# STM32_V1_0.net
KiCad netlist of a schematic drawn in Altium Designer
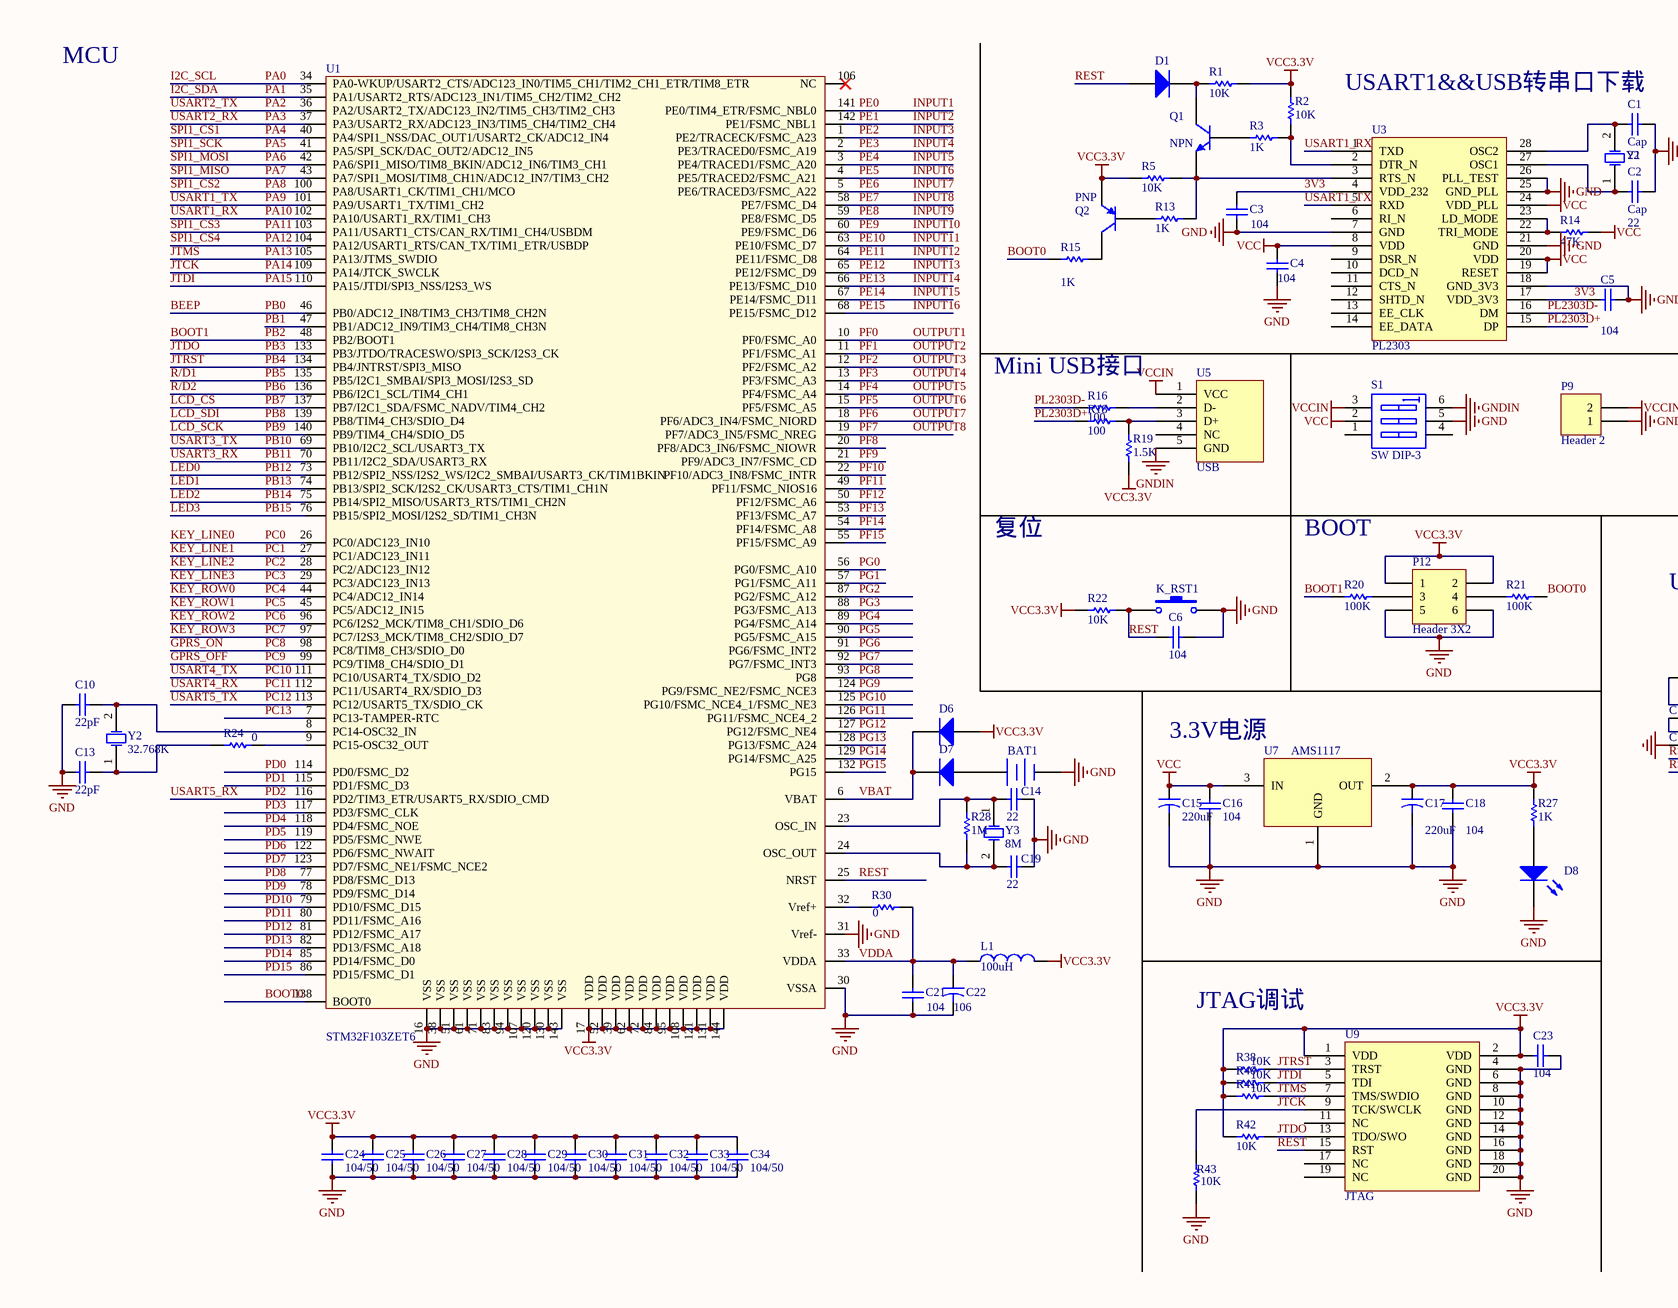
[diagram p0: STM32主板V1.0.SchDoc, left]
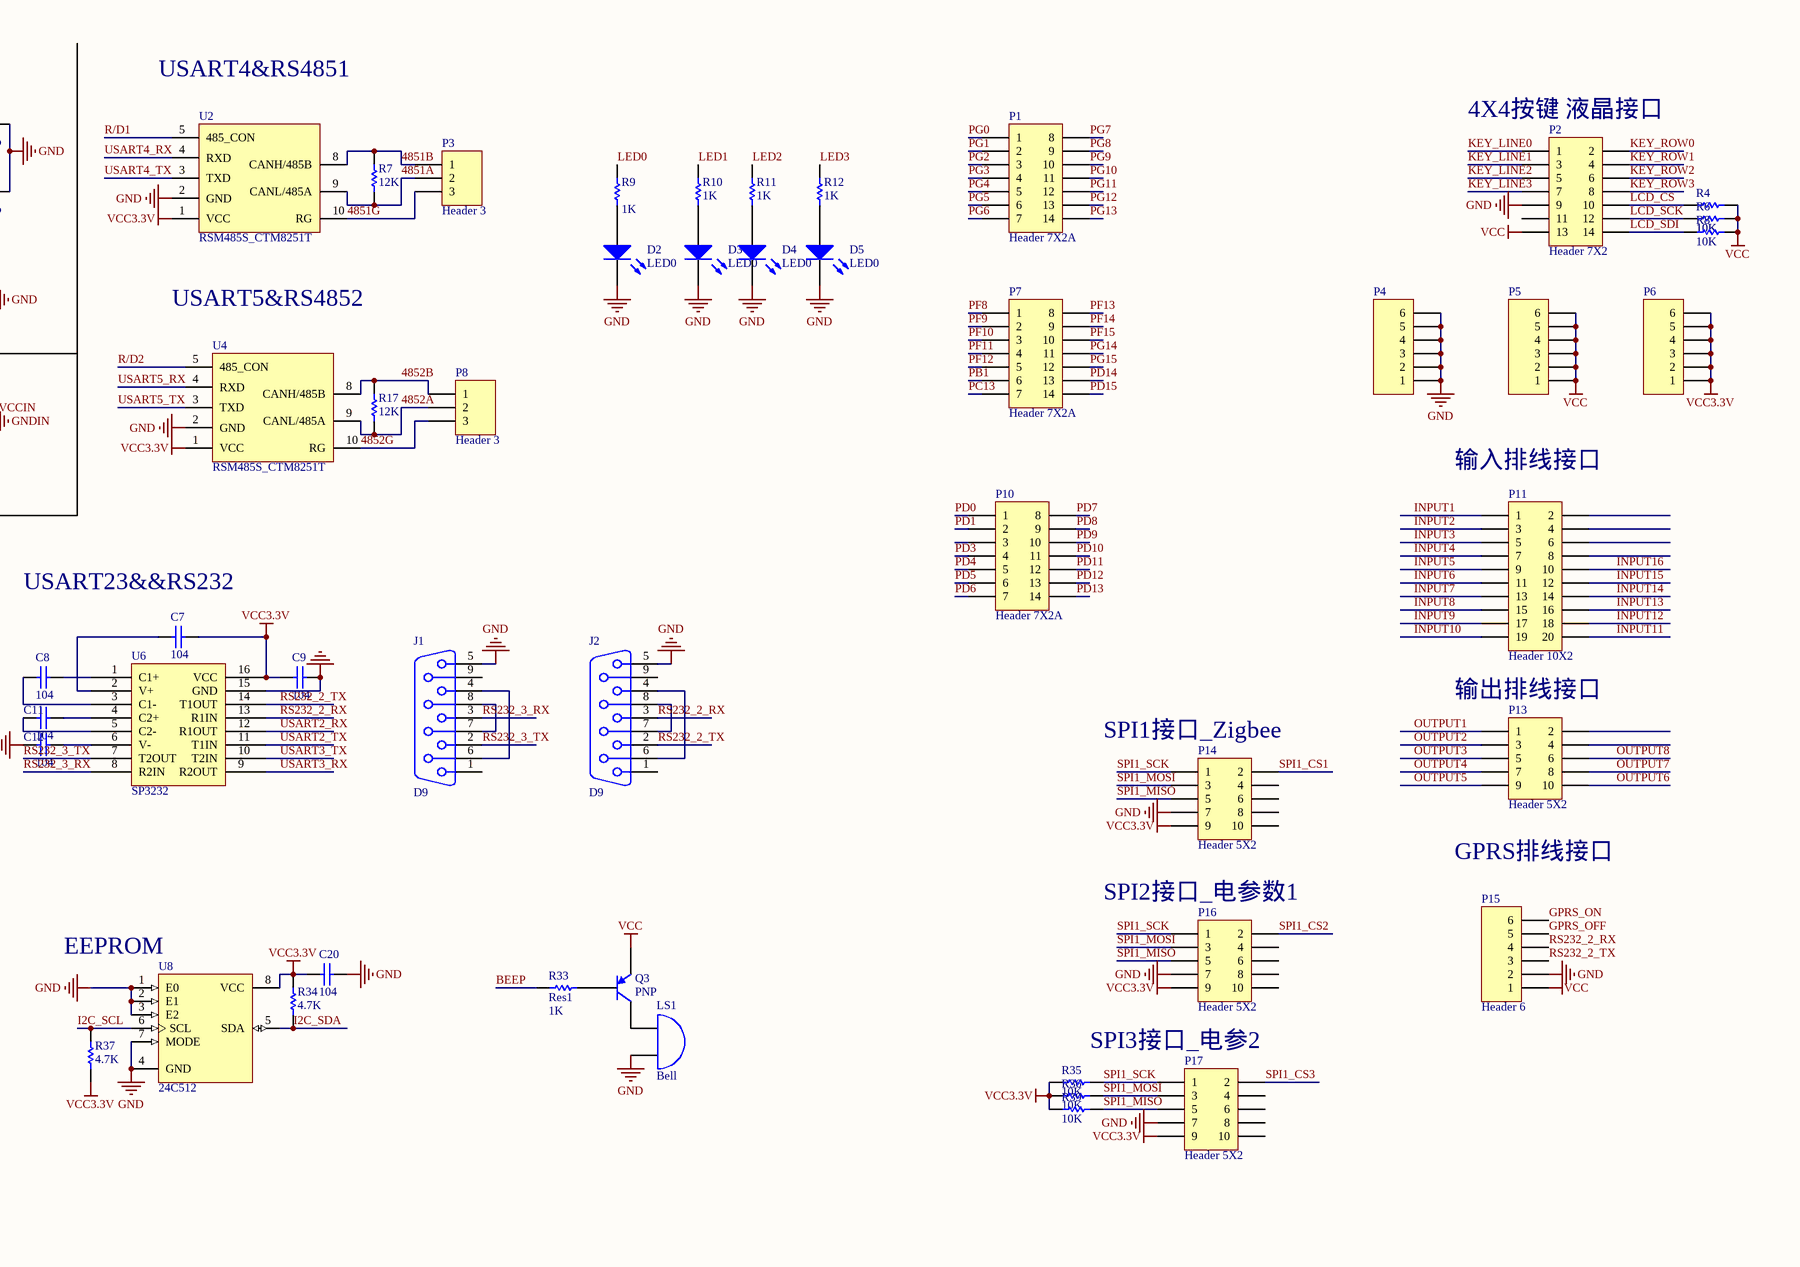
[diagram p1: STM32主板V1.0.SchDoc, right]

(export (version "E")
  (design (tool "Eeschema 10.0.6"))
  (components
    (comp (ref "BAT1")
      (value "Battery")
      (footprint "电池槽")
      (description "Multicell Battery")
      (fields (field (name "PUBLISHER") "Altium Limited"))
      (libsource (lib "Miscellaneous Devices") (part "Battery"))
    )
    (comp (ref "C1")
      (value "Cap")
      (footprint "普通贴片电容")
      (description "Capacitor")
      (fields (field (name "ALTIUM_VALUE") "22") (field (name "PUBLISHER") "Altium Limited"))
      (libsource (lib "Miscellaneous Devices") (part "Cap"))
    )
    (comp (ref "C2")
      (value "Cap")
      (footprint "普通贴片电容")
      (description "Capacitor")
      (fields (field (name "ALTIUM_VALUE") "22") (field (name "PUBLISHER") "Altium Limited"))
      (libsource (lib "Miscellaneous Devices") (part "Cap"))
    )
    (comp (ref "C3")
      (value "104")
      (footprint "普通贴片电容")
      (description "Capacitor")
      (fields (field (name "Comment") "Cap") (field (name "PUBLISHER") "Altium Limited"))
      (libsource (lib "Miscellaneous Devices") (part "Cap"))
    )
    (comp (ref "C4")
      (value "104")
      (footprint "普通贴片电容")
      (description "Capacitor")
      (fields (field (name "Comment") "Cap") (field (name "PUBLISHER") "Altium Limited"))
      (libsource (lib "Miscellaneous Devices") (part "Cap"))
    )
    (comp (ref "C5")
      (value "104")
      (footprint "普通贴片电容")
      (description "Capacitor")
      (fields (field (name "Comment") "Cap") (field (name "PUBLISHER") "Altium Limited"))
      (libsource (lib "Miscellaneous Devices") (part "Cap"))
    )
    (comp (ref "C6")
      (value "104")
      (footprint "普通贴片电容")
      (description "Capacitor")
      (fields (field (name "Comment") "Cap") (field (name "PUBLISHER") "Altium Limited"))
      (libsource (lib "Miscellaneous Devices") (part "Cap"))
    )
    (comp (ref "C7")
      (value "104")
      (footprint "普通贴片电容")
      (description "Capacitor (Semiconductor SIM Model)")
      (fields (field (name "PUBLISHER") "Altium Limited"))
      (libsource (lib "Miscellaneous Devices") (part "Cap Semi"))
    )
    (comp (ref "C8")
      (value "104")
      (footprint "普通贴片电容")
      (description "Capacitor (Semiconductor SIM Model)")
      (fields (field (name "PUBLISHER") "Altium Limited"))
      (libsource (lib "Miscellaneous Devices") (part "Cap Semi"))
    )
    (comp (ref "C9")
      (value "104")
      (footprint "普通贴片电容")
      (description "Capacitor (Semiconductor SIM Model)")
      (fields (field (name "PUBLISHER") "Altium Limited"))
      (libsource (lib "Miscellaneous Devices") (part "Cap Semi"))
    )
    (comp (ref "C10")
      (value "22pF")
      (footprint "普通贴片电容")
      (description "Capacitor")
      (fields (field (name "Comment") "Cap") (field (name "PUBLISHER") "Altium Limited"))
      (libsource (lib "Miscellaneous Devices") (part "Cap"))
    )
    (comp (ref "C11")
      (value "104")
      (footprint "普通贴片电容")
      (description "Capacitor (Semiconductor SIM Model)")
      (fields (field (name "PUBLISHER") "Altium Limited"))
      (libsource (lib "Miscellaneous Devices") (part "Cap Semi"))
    )
    (comp (ref "C12")
      (value "104")
      (footprint "普通贴片电容")
      (description "Capacitor (Semiconductor SIM Model)")
      (fields (field (name "PUBLISHER") "Altium Limited"))
      (libsource (lib "Miscellaneous Devices") (part "Cap Semi"))
    )
    (comp (ref "C13")
      (value "22pF")
      (footprint "普通贴片电容")
      (description "Capacitor")
      (fields (field (name "Comment") "Cap") (field (name "PUBLISHER") "Altium Limited"))
      (libsource (lib "Miscellaneous Devices") (part "Cap"))
    )
    (comp (ref "C14")
      (value "22")
      (footprint "普通贴片电容")
      (description "Capacitor")
      (fields (field (name "PUBLISHER") "Altium Limited"))
      (libsource (lib "Miscellaneous Devices") (part "Cap"))
    )
    (comp (ref "C15")
      (value "220uF")
      (footprint "电容100uf")
      (description "Capacitor")
      (fields (field (name "Comment") "Cap2") (field (name "PUBLISHER") "Altium Limited"))
      (libsource (lib "Miscellaneous Devices") (part "Cap2"))
    )
    (comp (ref "C16")
      (value "104")
      (footprint "普通贴片电容")
      (description "Capacitor")
      (fields (field (name "Comment") "Cap") (field (name "PUBLISHER") "Altium Limited"))
      (libsource (lib "Miscellaneous Devices") (part "Cap"))
    )
    (comp (ref "C17")
      (value "220uF")
      (footprint "电容100uf")
      (description "Capacitor")
      (fields (field (name "Comment") "Cap2") (field (name "PUBLISHER") "Altium Limited"))
      (libsource (lib "Miscellaneous Devices") (part "Cap2"))
    )
    (comp (ref "C18")
      (value "104")
      (footprint "普通贴片电容")
      (description "Capacitor")
      (fields (field (name "Comment") "Cap") (field (name "PUBLISHER") "Altium Limited"))
      (libsource (lib "Miscellaneous Devices") (part "Cap"))
    )
    (comp (ref "C19")
      (value "22")
      (footprint "普通贴片电容")
      (description "Capacitor")
      (fields (field (name "PUBLISHER") "Altium Limited"))
      (libsource (lib "Miscellaneous Devices") (part "Cap"))
    )
    (comp (ref "C20")
      (value "104")
      (footprint "普通贴片电容")
      (description "Capacitor")
      (fields (field (name "Comment") "Cap") (field (name "PUBLISHER") "Altium Limited"))
      (libsource (lib "Miscellaneous Devices") (part "Cap"))
    )
    (comp (ref "C21")
      (value "104")
      (footprint "普通贴片电容")
      (description "Capacitor")
      (fields (field (name "Comment") "Cap") (field (name "PUBLISHER") "Altium Limited"))
      (libsource (lib "Miscellaneous Devices") (part "Cap"))
    )
    (comp (ref "C22")
      (value "106")
      (footprint "普通贴片电容")
      (description "Capacitor")
      (fields (field (name "Comment") "Cap2") (field (name "PUBLISHER") "Altium Limited"))
      (libsource (lib "Miscellaneous Devices") (part "Cap2"))
    )
    (comp (ref "C23")
      (value "104")
      (footprint "普通贴片电容")
      (description "Capacitor")
      (fields (field (name "Comment") "Cap") (field (name "PUBLISHER") "Altium Limited"))
      (libsource (lib "Miscellaneous Devices") (part "Cap"))
    )
    (comp (ref "C24")
      (value "104/50")
      (footprint "普通贴片电容")
      (description "Capacitor")
      (fields (field (name "Comment") "Cap") (field (name "PUBLISHER") "Altium Limited"))
      (libsource (lib "Miscellaneous Devices") (part "Cap"))
    )
    (comp (ref "C25")
      (value "104/50")
      (footprint "普通贴片电容")
      (description "Capacitor")
      (fields (field (name "Comment") "Cap") (field (name "PUBLISHER") "Altium Limited"))
      (libsource (lib "Miscellaneous Devices") (part "Cap"))
    )
    (comp (ref "C26")
      (value "104/50")
      (footprint "普通贴片电容")
      (description "Capacitor")
      (fields (field (name "Comment") "Cap") (field (name "PUBLISHER") "Altium Limited"))
      (libsource (lib "Miscellaneous Devices") (part "Cap"))
    )
    (comp (ref "C27")
      (value "104/50")
      (footprint "普通贴片电容")
      (description "Capacitor")
      (fields (field (name "Comment") "Cap") (field (name "PUBLISHER") "Altium Limited"))
      (libsource (lib "Miscellaneous Devices") (part "Cap"))
    )
    (comp (ref "C28")
      (value "104/50")
      (footprint "普通贴片电容")
      (description "Capacitor")
      (fields (field (name "Comment") "Cap") (field (name "PUBLISHER") "Altium Limited"))
      (libsource (lib "Miscellaneous Devices") (part "Cap"))
    )
    (comp (ref "C29")
      (value "104/50")
      (footprint "普通贴片电容")
      (description "Capacitor")
      (fields (field (name "Comment") "Cap") (field (name "PUBLISHER") "Altium Limited"))
      (libsource (lib "Miscellaneous Devices") (part "Cap"))
    )
    (comp (ref "C30")
      (value "104/50")
      (footprint "普通贴片电容")
      (description "Capacitor")
      (fields (field (name "Comment") "Cap") (field (name "PUBLISHER") "Altium Limited"))
      (libsource (lib "Miscellaneous Devices") (part "Cap"))
    )
    (comp (ref "C31")
      (value "104/50")
      (footprint "普通贴片电容")
      (description "Capacitor")
      (fields (field (name "Comment") "Cap") (field (name "PUBLISHER") "Altium Limited"))
      (libsource (lib "Miscellaneous Devices") (part "Cap"))
    )
    (comp (ref "C32")
      (value "104/50")
      (footprint "普通贴片电容")
      (description "Capacitor")
      (fields (field (name "Comment") "Cap") (field (name "PUBLISHER") "Altium Limited"))
      (libsource (lib "Miscellaneous Devices") (part "Cap"))
    )
    (comp (ref "C33")
      (value "104/50")
      (footprint "普通贴片电容")
      (description "Capacitor")
      (fields (field (name "Comment") "Cap") (field (name "PUBLISHER") "Altium Limited"))
      (libsource (lib "Miscellaneous Devices") (part "Cap"))
    )
    (comp (ref "C34")
      (value "104/50")
      (footprint "普通贴片电容")
      (description "Capacitor")
      (fields (field (name "Comment") "Cap") (field (name "PUBLISHER") "Altium Limited"))
      (libsource (lib "Miscellaneous Devices") (part "Cap"))
    )
    (comp (ref "D1")
      (value "Diode")
      (footprint "贴片二极管")
      (description "Default Diode")
      (fields (field (name "PUBLISHER") "Altium Limited"))
      (libsource (lib "Miscellaneous Devices") (part "Diode"))
    )
    (comp (ref "D2")
      (value "LED0")
      (footprint "贴片LED灯")
      (description "Typical INFRARED GaAs LED")
      (fields (field (name "PUBLISHER") "Altium Limited"))
      (libsource (lib "Miscellaneous Devices") (part "LED0"))
    )
    (comp (ref "D3")
      (value "LED0")
      (footprint "贴片LED灯")
      (description "Typical INFRARED GaAs LED")
      (fields (field (name "PUBLISHER") "Altium Limited"))
      (libsource (lib "Miscellaneous Devices") (part "LED0"))
    )
    (comp (ref "D4")
      (value "LED0")
      (footprint "贴片LED灯")
      (description "Typical INFRARED GaAs LED")
      (fields (field (name "PUBLISHER") "Altium Limited"))
      (libsource (lib "Miscellaneous Devices") (part "LED0"))
    )
    (comp (ref "D5")
      (value "LED0")
      (footprint "贴片LED灯")
      (description "Typical INFRARED GaAs LED")
      (fields (field (name "PUBLISHER") "Altium Limited"))
      (libsource (lib "Miscellaneous Devices") (part "LED0"))
    )
    (comp (ref "D6")
      (value "Diode 1N4148")
      (footprint "贴片二极管")
      (description "High Conductance Fast Diode")
      (fields (field (name "PUBLISHER") "Altium Limited"))
      (libsource (lib "Miscellaneous Devices") (part "Diode 1N4148"))
    )
    (comp (ref "D7")
      (value "Diode 1N4148")
      (footprint "贴片二极管")
      (description "High Conductance Fast Diode")
      (fields (field (name "PUBLISHER") "Altium Limited"))
      (libsource (lib "Miscellaneous Devices") (part "Diode 1N4148"))
    )
    (comp (ref "D8")
      (value "LED0")
      (footprint "贴片LED灯")
      (description "Typical INFRARED GaAs LED")
      (fields (field (name "PUBLISHER") "Altium Limited"))
      (libsource (lib "Miscellaneous Devices") (part "LED0"))
    )
    (comp (ref "J1")
      (value "D9")
      (footprint "串口")
      (description "Receptacle Assembly, 9 Position, Right Angle")
      (fields (field (name "PUBLISHER") "Altium Limited"))
      (libsource (lib "Miscellaneous Connectors") (part "D Connector 9"))
    )
    (comp (ref "J2")
      (value "D9")
      (footprint "串口")
      (description "Receptacle Assembly, 9 Position, Right Angle")
      (fields (field (name "PUBLISHER") "Altium Limited"))
      (libsource (lib "Miscellaneous Connectors") (part "D Connector 9"))
    )
    (comp (ref "K_RST1")
      (value "SW-PB")
      (footprint "按键")
      (description "Switch")
      (fields (field (name "PUBLISHER") "Altium Limited"))
      (libsource (lib "Miscellaneous Devices") (part "SW-PB"))
    )
    (comp (ref "L1")
      (value "100uH")
      (footprint "贴片电阻")
      (description "Inductor")
      (fields (field (name "PUBLISHER") "Altium Limited"))
      (libsource (lib "Miscellaneous Devices") (part "Inductor"))
    )
    (comp (ref "LS1")
      (value "Bell")
      (footprint "BELL")
      (description "Electrical Bell")
      (fields (field (name "PUBLISHER") "Altium Limited"))
      (libsource (lib "Miscellaneous Devices") (part "Bell"))
    )
    (comp (ref "P1")
      (value "Header 7X2A")
      (footprint "CON14a")
      (description "Header, 7-Pin, Dual row")
      (fields (field (name "PUBLISHER") "Altium Limited"))
      (libsource (lib "Miscellaneous Connectors") (part "Header 7X2A"))
    )
    (comp (ref "P2")
      (value "Header 7X2")
      (footprint "CON14")
      (description "Header, 7-Pin, Dual row")
      (fields (field (name "PUBLISHER") "Altium Limited"))
      (libsource (lib "Miscellaneous Connectors") (part "Header 7X2"))
    )
    (comp (ref "P3")
      (value "Header 3")
      (footprint "HDR1X3")
      (description "Header, 3-Pin")
      (fields (field (name "PUBLISHER") "Altium Limited"))
      (libsource (lib "Miscellaneous Connectors") (part "Header 3"))
    )
    (comp (ref "P4")
      (value "Header 6")
      (footprint "HDR1X6")
      (description "Header, 6-Pin")
      (fields (field (name "PUBLISHER") "Altium Limited"))
      (libsource (lib "Miscellaneous Connectors") (part "Header 6"))
    )
    (comp (ref "P5")
      (value "Header 6")
      (footprint "HDR1X6")
      (description "Header, 6-Pin")
      (fields (field (name "PUBLISHER") "Altium Limited"))
      (libsource (lib "Miscellaneous Connectors") (part "Header 6"))
    )
    (comp (ref "P6")
      (value "Header 6")
      (footprint "HDR1X6")
      (description "Header, 6-Pin")
      (fields (field (name "PUBLISHER") "Altium Limited"))
      (libsource (lib "Miscellaneous Connectors") (part "Header 6"))
    )
    (comp (ref "P7")
      (value "Header 7X2A")
      (footprint "CON14a")
      (description "Header, 7-Pin, Dual row")
      (fields (field (name "PUBLISHER") "Altium Limited"))
      (libsource (lib "Miscellaneous Connectors") (part "Header 7X2A"))
    )
    (comp (ref "P8")
      (value "Header 3")
      (footprint "HDR1X3")
      (description "Header, 3-Pin")
      (fields (field (name "PUBLISHER") "Altium Limited"))
      (libsource (lib "Miscellaneous Connectors") (part "Header 3"))
    )
    (comp (ref "P9")
      (value "Header 2")
      (footprint "HDR1X2")
      (description "Header, 2-Pin")
      (fields (field (name "PUBLISHER") "Altium Limited"))
      (libsource (lib "Miscellaneous Connectors") (part "Header 2"))
    )
    (comp (ref "P10")
      (value "Header 7X2A")
      (footprint "CON14a")
      (description "Header, 7-Pin, Dual row")
      (fields (field (name "PUBLISHER") "Altium Limited"))
      (libsource (lib "Miscellaneous Connectors") (part "Header 7X2A"))
    )
    (comp (ref "P11")
      (value "Header 10X2")
      (footprint "CON20")
      (description "Header, 10-Pin, Dual row")
      (fields (field (name "PUBLISHER") "Altium Limited"))
      (libsource (lib "Miscellaneous Connectors") (part "Header 10X2"))
    )
    (comp (ref "P12")
      (value "Header 3X2")
      (footprint "HDR2X3")
      (description "Header, 3-Pin, Dual row")
      (fields (field (name "PUBLISHER") "Altium Limited"))
      (libsource (lib "Miscellaneous Connectors") (part "Header 3X2"))
    )
    (comp (ref "P13")
      (value "Header 5X2")
      (footprint "CON10")
      (description "Header, 5-Pin, Dual row")
      (fields (field (name "PUBLISHER") "Altium Limited"))
      (libsource (lib "Miscellaneous Connectors") (part "Header 5X2"))
    )
    (comp (ref "P14")
      (value "Header 5X2")
      (footprint "CON10")
      (description "Header, 5-Pin, Dual row")
      (fields (field (name "PUBLISHER") "Altium Limited"))
      (libsource (lib "Miscellaneous Connectors") (part "Header 5X2"))
    )
    (comp (ref "P15")
      (value "Header 6")
      (footprint "HDR1X6")
      (description "Header, 6-Pin")
      (fields (field (name "PUBLISHER") "Altium Limited"))
      (libsource (lib "Miscellaneous Connectors") (part "Header 6"))
    )
    (comp (ref "P16")
      (value "Header 5X2")
      (footprint "CON10")
      (description "Header, 5-Pin, Dual row")
      (fields (field (name "PUBLISHER") "Altium Limited"))
      (libsource (lib "Miscellaneous Connectors") (part "Header 5X2"))
    )
    (comp (ref "P17")
      (value "Header 5X2")
      (footprint "CON10")
      (description "Header, 5-Pin, Dual row")
      (fields (field (name "PUBLISHER") "Altium Limited"))
      (libsource (lib "Miscellaneous Connectors") (part "Header 5X2"))
    )
    (comp (ref "Q1")
      (value "NPN")
      (footprint "三极管 NPN")
      (description "NPN Bipolar Transistor")
      (fields (field (name "PUBLISHER") "Altium Limited"))
      (libsource (lib "Miscellaneous Devices") (part "NPN"))
    )
    (comp (ref "Q2")
      (value "PNP")
      (footprint "三极管 PNP")
      (description "PNP Bipolar Transistor")
      (fields (field (name "PUBLISHER") "Altium Limited"))
      (libsource (lib "Miscellaneous Devices") (part "PNP"))
    )
    (comp (ref "Q3")
      (value "PNP")
      (footprint "三极管 PNP")
      (description "PNP Bipolar Transistor")
      (fields (field (name "PUBLISHER") "Altium Limited"))
      (libsource (lib "Miscellaneous Devices") (part "PNP"))
    )
    (comp (ref "R1")
      (value "10K")
      (footprint "贴片电阻")
      (description "Resistor")
      (fields (field (name "Comment") "Res1") (field (name "PUBLISHER") "Altium Limited"))
      (libsource (lib "Miscellaneous Devices") (part "Res1"))
    )
    (comp (ref "R2")
      (value "10K")
      (footprint "贴片电阻")
      (description "Resistor")
      (fields (field (name "Comment") "Res1") (field (name "PUBLISHER") "Altium Limited"))
      (libsource (lib "Miscellaneous Devices") (part "Res1"))
    )
    (comp (ref "R3")
      (value "1K")
      (footprint "贴片电阻")
      (description "Resistor")
      (fields (field (name "Comment") "Res1") (field (name "PUBLISHER") "Altium Limited"))
      (libsource (lib "Miscellaneous Devices") (part "Res1"))
    )
    (comp (ref "R4")
      (value "10K")
      (footprint "贴片电阻")
      (description "Resistor")
      (fields (field (name "Comment") "Res1") (field (name "PUBLISHER") "Altium Limited"))
      (libsource (lib "Miscellaneous Devices") (part "Res1"))
    )
    (comp (ref "R5")
      (value "10K")
      (footprint "贴片电阻")
      (description "Resistor")
      (fields (field (name "Comment") "Res1") (field (name "PUBLISHER") "Altium Limited"))
      (libsource (lib "Miscellaneous Devices") (part "Res1"))
    )
    (comp (ref "R6")
      (value "10K")
      (footprint "贴片电阻")
      (description "Resistor")
      (fields (field (name "Comment") "Res1") (field (name "PUBLISHER") "Altium Limited"))
      (libsource (lib "Miscellaneous Devices") (part "Res1"))
    )
    (comp (ref "R7")
      (value "12K")
      (footprint "贴片电阻")
      (description "Resistor")
      (fields (field (name "Comment") "Res1") (field (name "PUBLISHER") "Altium Limited"))
      (libsource (lib "Miscellaneous Devices") (part "Res1"))
    )
    (comp (ref "R8")
      (value "10K")
      (footprint "贴片电阻")
      (description "Resistor")
      (fields (field (name "Comment") "Res1") (field (name "PUBLISHER") "Altium Limited"))
      (libsource (lib "Miscellaneous Devices") (part "Res1"))
    )
    (comp (ref "R9")
      (value "1K")
      (footprint "贴片电阻")
      (description "Resistor")
      (fields (field (name "Comment") "Res1") (field (name "PUBLISHER") "Altium Limited"))
      (libsource (lib "Miscellaneous Devices") (part "Res1"))
    )
    (comp (ref "R10")
      (value "1K")
      (footprint "贴片电阻")
      (description "Resistor")
      (fields (field (name "Comment") "Res1") (field (name "PUBLISHER") "Altium Limited"))
      (libsource (lib "Miscellaneous Devices") (part "Res1"))
    )
    (comp (ref "R11")
      (value "1K")
      (footprint "贴片电阻")
      (description "Resistor")
      (fields (field (name "Comment") "Res1") (field (name "PUBLISHER") "Altium Limited"))
      (libsource (lib "Miscellaneous Devices") (part "Res1"))
    )
    (comp (ref "R12")
      (value "1K")
      (footprint "贴片电阻")
      (description "Resistor")
      (fields (field (name "Comment") "Res1") (field (name "PUBLISHER") "Altium Limited"))
      (libsource (lib "Miscellaneous Devices") (part "Res1"))
    )
    (comp (ref "R13")
      (value "1K")
      (footprint "贴片电阻")
      (description "Resistor")
      (fields (field (name "Comment") "Res1") (field (name "PUBLISHER") "Altium Limited"))
      (libsource (lib "Miscellaneous Devices") (part "Res1"))
    )
    (comp (ref "R14")
      (value "47K")
      (footprint "贴片电阻")
      (description "Resistor")
      (fields (field (name "Comment") "Res1") (field (name "PUBLISHER") "Altium Limited"))
      (libsource (lib "Miscellaneous Devices") (part "Res1"))
    )
    (comp (ref "R15")
      (value "1K")
      (footprint "贴片电阻")
      (description "Resistor")
      (fields (field (name "Comment") "Res1") (field (name "PUBLISHER") "Altium Limited"))
      (libsource (lib "Miscellaneous Devices") (part "Res1"))
    )
    (comp (ref "R16")
      (value "100")
      (footprint "贴片电阻")
      (description "Resistor")
      (fields (field (name "Comment") "Res1") (field (name "PUBLISHER") "Altium Limited"))
      (libsource (lib "Miscellaneous Devices") (part "Res1"))
    )
    (comp (ref "R17")
      (value "12K")
      (footprint "贴片电阻")
      (description "Resistor")
      (fields (field (name "Comment") "Res1") (field (name "PUBLISHER") "Altium Limited"))
      (libsource (lib "Miscellaneous Devices") (part "Res1"))
    )
    (comp (ref "R18")
      (value "100")
      (footprint "贴片电阻")
      (description "Resistor")
      (fields (field (name "Comment") "Res1") (field (name "PUBLISHER") "Altium Limited"))
      (libsource (lib "Miscellaneous Devices") (part "Res1"))
    )
    (comp (ref "R19")
      (value "1.5K")
      (footprint "贴片电阻")
      (description "Resistor")
      (fields (field (name "Comment") "Res1") (field (name "PUBLISHER") "Altium Limited"))
      (libsource (lib "Miscellaneous Devices") (part "Res1"))
    )
    (comp (ref "R20")
      (value "100K")
      (footprint "贴片电阻")
      (description "Resistor")
      (fields (field (name "Comment") "Res1") (field (name "PUBLISHER") "Altium Limited"))
      (libsource (lib "Miscellaneous Devices") (part "Res1"))
    )
    (comp (ref "R21")
      (value "100K")
      (footprint "贴片电阻")
      (description "Resistor")
      (fields (field (name "Comment") "Res1") (field (name "PUBLISHER") "Altium Limited"))
      (libsource (lib "Miscellaneous Devices") (part "Res1"))
    )
    (comp (ref "R22")
      (value "10K")
      (footprint "贴片电阻")
      (description "Resistor")
      (fields (field (name "Comment") "Res1") (field (name "PUBLISHER") "Altium Limited"))
      (libsource (lib "Miscellaneous Devices") (part "Res1"))
    )
    (comp (ref "R24")
      (value "0")
      (footprint "贴片电阻")
      (description "Resistor")
      (fields (field (name "Comment") "Res1") (field (name "PUBLISHER") "Altium Limited"))
      (libsource (lib "Miscellaneous Devices") (part "Res1"))
    )
    (comp (ref "R27")
      (value "1K")
      (footprint "贴片电阻")
      (description "Resistor")
      (fields (field (name "Comment") "Res1") (field (name "PUBLISHER") "Altium Limited"))
      (libsource (lib "Miscellaneous Devices") (part "Res1"))
    )
    (comp (ref "R28")
      (value "1M")
      (footprint "贴片电阻")
      (description "Resistor")
      (fields (field (name "Comment") "Res1") (field (name "PUBLISHER") "Altium Limited"))
      (libsource (lib "Miscellaneous Devices") (part "Res1"))
    )
    (comp (ref "R30")
      (value "0")
      (footprint "贴片电阻")
      (description "Resistor")
      (fields (field (name "Comment") "Res1") (field (name "PUBLISHER") "Altium Limited"))
      (libsource (lib "Miscellaneous Devices") (part "Res1"))
    )
    (comp (ref "R33")
      (value "Res1")
      (footprint "贴片电阻")
      (description "Resistor")
      (fields (field (name "ALTIUM_VALUE") "1K") (field (name "PUBLISHER") "Altium Limited"))
      (libsource (lib "Miscellaneous Devices") (part "Res1"))
    )
    (comp (ref "R34")
      (value "4.7K")
      (footprint "贴片电阻")
      (description "Resistor")
      (fields (field (name "Comment") "Res1") (field (name "PUBLISHER") "Altium Limited"))
      (libsource (lib "Miscellaneous Devices") (part "Res1"))
    )
    (comp (ref "R35")
      (value "10K")
      (footprint "贴片电阻")
      (description "Resistor")
      (fields (field (name "Comment") "Res1") (field (name "PUBLISHER") "Altium Limited"))
      (libsource (lib "Miscellaneous Devices") (part "Res1"))
    )
    (comp (ref "R36")
      (value "10K")
      (footprint "贴片电阻")
      (description "Resistor")
      (fields (field (name "Comment") "Res1") (field (name "PUBLISHER") "Altium Limited"))
      (libsource (lib "Miscellaneous Devices") (part "Res1"))
    )
    (comp (ref "R37")
      (value "4.7K")
      (footprint "贴片电阻")
      (description "Resistor")
      (fields (field (name "Comment") "Res1") (field (name "PUBLISHER") "Altium Limited"))
      (libsource (lib "Miscellaneous Devices") (part "Res1"))
    )
    (comp (ref "R38")
      (value "10K")
      (footprint "贴片电阻")
      (description "Resistor")
      (fields (field (name "Comment") "Res1") (field (name "PUBLISHER") "Altium Limited"))
      (libsource (lib "Miscellaneous Devices") (part "Res1"))
    )
    (comp (ref "R39")
      (value "10K")
      (footprint "贴片电阻")
      (description "Resistor")
      (fields (field (name "Comment") "Res1") (field (name "PUBLISHER") "Altium Limited"))
      (libsource (lib "Miscellaneous Devices") (part "Res1"))
    )
    (comp (ref "R40")
      (value "10K")
      (footprint "贴片电阻")
      (description "Resistor")
      (fields (field (name "Comment") "Res1") (field (name "PUBLISHER") "Altium Limited"))
      (libsource (lib "Miscellaneous Devices") (part "Res1"))
    )
    (comp (ref "R41")
      (value "10K")
      (footprint "贴片电阻")
      (description "Resistor")
      (fields (field (name "Comment") "Res1") (field (name "PUBLISHER") "Altium Limited"))
      (libsource (lib "Miscellaneous Devices") (part "Res1"))
    )
    (comp (ref "R42")
      (value "10K")
      (footprint "贴片电阻")
      (description "Resistor")
      (fields (field (name "Comment") "Res1") (field (name "PUBLISHER") "Altium Limited"))
      (libsource (lib "Miscellaneous Devices") (part "Res1"))
    )
    (comp (ref "R43")
      (value "10K")
      (footprint "贴片电阻")
      (description "Resistor")
      (fields (field (name "Comment") "Res1") (field (name "PUBLISHER") "Altium Limited"))
      (libsource (lib "Miscellaneous Devices") (part "Res1"))
    )
    (comp (ref "S1")
      (value "SW DIP-3")
      (footprint "开关")
      (description "DIP Switch, 3 Position, SPST")
      (fields (field (name "PUBLISHER") "Altium Limited"))
      (libsource (lib "Miscellaneous Devices") (part "SW DIP-3"))
    )
    (comp (ref "U1")
      (value "STM32F103ZET6")
      (footprint "LQFP144")
      (libsource (lib "stm32") (part "STM32F103ZET6"))
    )
    (comp (ref "U2")
      (value "RSM485S_CTM8251T")
      (footprint "RS485")
      (libsource (lib "RSM485Sch") (part "RSM485S_CTM8251T"))
    )
    (comp (ref "U3") (value "PL2303") (footprint "SSOP28") (libsource (lib "STM32") (part "PL2303")))
    (comp (ref "U4")
      (value "RSM485S_CTM8251T")
      (footprint "RS485")
      (libsource (lib "RSM485Sch") (part "RSM485S_CTM8251T"))
    )
    (comp (ref "U5") (value "USB") (footprint "miniUSB") (libsource (lib "STM32") (part "USB")))
    (comp (ref "U6") (value "SP3232") (footprint "SSOP16") (libsource (lib "TX-51") (part "MAX232")))
    (comp (ref "U7") (value "AMS1117") (footprint "AMS1117") (libsource (lib "STM32") (part "AMS1117")))
    (comp (ref "U8")
      (value "24C512")
      (footprint "SOP8")
      (description "Serial 2K (256 x 8) EEPROM")
      (fields (field (name "PUBLISHER") "Altium Limited"))
      (libsource (lib "ST Memory EEPROM Serial") (part "ST24C02M1"))
    )
    (comp (ref "U9") (value "JTAG") (footprint "CON20") (libsource (lib "STM32") (part "JTAG")))
    (comp (ref "Y1")
      (value "XTAL")
      (footprint "晶振")
      (description "Crystal Oscillator")
      (fields (field (name "PUBLISHER") "Altium Limited"))
      (libsource (lib "Miscellaneous Devices") (part "XTAL"))
    )
    (comp (ref "Y2")
      (value "32.768K")
      (footprint "R38")
      (description "Crystal Oscillator")
      (fields (field (name "PUBLISHER") "Altium Limited"))
      (libsource (lib "Miscellaneous Devices") (part "XTAL"))
    )
    (comp (ref "Y3")
      (value "8M")
      (footprint "晶振")
      (description "Crystal Oscillator")
      (fields (field (name "PUBLISHER") "Altium Limited"))
      (libsource (lib "Miscellaneous Devices") (part "XTAL"))
    )
  )
  (nets
    (net (code "1") (name "/3V3") (class "Default")
      (node (ref "C3") (pin "2") (pinfunction "2_2") (pintype "passive"))
      (node (ref "C5") (pin "1") (pinfunction "1_1") (pintype "passive"))
      (node (ref "U3") (pin "17") (pinfunction "VDD_3V3_17") (pintype "passive"))
      (node (ref "U3") (pin "4") (pinfunction "VDD_232_4") (pintype "passive"))
    )
    (net (code "2") (name "/4851A") (class "Default")
      (node (ref "P3") (pin "2") (pinfunction "2_2") (pintype "passive"))
      (node (ref "R7") (pin "1") (pinfunction "1_1") (pintype "passive"))
      (node (ref "U2") (pin "9") (pinfunction "CANL/485A_9") (pintype "passive"))
    )
    (net (code "3") (name "/4851B") (class "Default")
      (node (ref "P3") (pin "1") (pinfunction "1_1") (pintype "passive"))
      (node (ref "R7") (pin "2") (pinfunction "2_2") (pintype "passive"))
      (node (ref "U2") (pin "8") (pinfunction "CANH/485B_8") (pintype "passive"))
    )
    (net (code "4") (name "/4851G") (class "Default")
      (node (ref "P3") (pin "3") (pinfunction "3_3") (pintype "passive"))
      (node (ref "U2") (pin "10") (pinfunction "RG_10") (pintype "passive"))
    )
    (net (code "5") (name "/4852A") (class "Default")
      (node (ref "P8") (pin "2") (pinfunction "2_2") (pintype "passive"))
      (node (ref "R17") (pin "1") (pinfunction "1_1") (pintype "passive"))
      (node (ref "U4") (pin "9") (pinfunction "CANL/485A_9") (pintype "passive"))
    )
    (net (code "6") (name "/4852B") (class "Default")
      (node (ref "P8") (pin "1") (pinfunction "1_1") (pintype "passive"))
      (node (ref "R17") (pin "2") (pinfunction "2_2") (pintype "passive"))
      (node (ref "U4") (pin "8") (pinfunction "CANH/485B_8") (pintype "passive"))
    )
    (net (code "7") (name "/4852G") (class "Default")
      (node (ref "P8") (pin "3") (pinfunction "3_3") (pintype "passive"))
      (node (ref "U4") (pin "10") (pinfunction "RG_10") (pintype "passive"))
    )
    (net (code "8") (name "/BEEP") (class "Default")
      (node (ref "R33") (pin "1") (pinfunction "1_1") (pintype "passive"))
      (node (ref "U1") (pin "46") (pinfunction "PB0/ADC12_IN8/TIM3_CH3/TIM8_CH2N_46") (pintype "passive"))
    )
    (net (code "9") (name "/BOOT0") (class "Default")
      (node (ref "R15") (pin "1") (pinfunction "1_1") (pintype "passive"))
      (node (ref "R21") (pin "2") (pinfunction "2_2") (pintype "passive"))
      (node (ref "U1") (pin "138") (pinfunction "BOOT0_138") (pintype "passive"))
    )
    (net (code "10") (name "/BOOT1") (class "Default")
      (node (ref "R20") (pin "1") (pinfunction "1_1") (pintype "passive"))
      (node (ref "U1") (pin "48") (pinfunction "PB2/BOOT1_48") (pintype "passive"))
    )
    (net (code "11") (name "/GPRS_OFF") (class "Default")
      (node (ref "P15") (pin "5") (pinfunction "5_5") (pintype "passive"))
      (node (ref "U1") (pin "99") (pinfunction "PC9/TIM8_CH4/SDIO_D1_99") (pintype "passive"))
    )
    (net (code "12") (name "/GPRS_ON") (class "Default")
      (node (ref "P15") (pin "6") (pinfunction "6_6") (pintype "passive"))
      (node (ref "U1") (pin "98") (pinfunction "PC8/TIM8_CH3/SDIO_D0_98") (pintype "passive"))
    )
    (net (code "13") (name "/I2C_SCL") (class "Default")
      (node (ref "R37") (pin "2") (pinfunction "2_2") (pintype "passive"))
      (node (ref "U1") (pin "34") (pinfunction "PA0-WKUP/USART2_CTS/ADC123_IN0/TIM5_CH1/TIM2_CH1_ETR/TIM8_ETR_34") (pintype "passive"))
      (node (ref "U8") (pin "6") (pinfunction "SCL_6") (pintype "input"))
    )
    (net (code "14") (name "/I2C_SDA") (class "Default")
      (node (ref "R34") (pin "1") (pinfunction "1_1") (pintype "passive"))
      (node (ref "U1") (pin "35") (pinfunction "PA1/USART2_RTS/ADC123_IN1/TIM5_CH2/TIM2_CH2_35") (pintype "passive"))
      (node (ref "U8") (pin "5") (pinfunction "SDA_5") (pintype "bidirectional"))
    )
    (net (code "15") (name "/INPUT1") (class "Default")
      (node (ref "P11") (pin "1") (pinfunction "1_1") (pintype "passive"))
      (node (ref "U1") (pin "141") (pinfunction "PE0/TIM4_ETR/FSMC_NBL0_141") (pintype "passive"))
    )
    (net (code "16") (name "/INPUT2") (class "Default")
      (node (ref "P11") (pin "3") (pinfunction "3_3") (pintype "passive"))
      (node (ref "U1") (pin "142") (pinfunction "PE1/FSMC_NBL1_142") (pintype "passive"))
    )
    (net (code "17") (name "/INPUT3") (class "Default")
      (node (ref "P11") (pin "5") (pinfunction "5_5") (pintype "passive"))
      (node (ref "U1") (pin "1") (pinfunction "PE2/TRACECK/FSMC_A23_1") (pintype "passive"))
    )
    (net (code "18") (name "/INPUT4") (class "Default")
      (node (ref "P11") (pin "7") (pinfunction "7_7") (pintype "passive"))
      (node (ref "U1") (pin "2") (pinfunction "PE3/TRACED0/FSMC_A19_2") (pintype "passive"))
    )
    (net (code "19") (name "/INPUT5") (class "Default")
      (node (ref "P11") (pin "9") (pinfunction "9_9") (pintype "passive"))
      (node (ref "U1") (pin "3") (pinfunction "PE4/TRACED1/FSMC_A20_3") (pintype "passive"))
    )
    (net (code "20") (name "/INPUT6") (class "Default")
      (node (ref "P11") (pin "11") (pinfunction "11_11") (pintype "passive"))
      (node (ref "U1") (pin "4") (pinfunction "PE5/TRACED2/FSMC_A21_4") (pintype "passive"))
    )
    (net (code "21") (name "/INPUT7") (class "Default")
      (node (ref "P11") (pin "13") (pinfunction "13_13") (pintype "passive"))
      (node (ref "U1") (pin "5") (pinfunction "PE6/TRACED3/FSMC_A22_5") (pintype "passive"))
    )
    (net (code "22") (name "/INPUT8") (class "Default")
      (node (ref "P11") (pin "15") (pinfunction "15_15") (pintype "passive"))
      (node (ref "U1") (pin "58") (pinfunction "PE7/FSMC_D4_58") (pintype "passive"))
    )
    (net (code "23") (name "/INPUT9") (class "Default")
      (node (ref "P11") (pin "17") (pinfunction "17_17") (pintype "passive"))
      (node (ref "U1") (pin "59") (pinfunction "PE8/FSMC_D5_59") (pintype "passive"))
    )
    (net (code "24") (name "/INPUT10") (class "Default")
      (node (ref "P11") (pin "19") (pinfunction "19_19") (pintype "passive"))
      (node (ref "U1") (pin "60") (pinfunction "PE9/FSMC_D6_60") (pintype "passive"))
    )
    (net (code "25") (name "/INPUT11") (class "Default")
      (node (ref "P11") (pin "20") (pinfunction "20_20") (pintype "passive"))
      (node (ref "U1") (pin "63") (pinfunction "PE10/FSMC_D7_63") (pintype "passive"))
    )
    (net (code "26") (name "/INPUT12") (class "Default")
      (node (ref "P11") (pin "18") (pinfunction "18_18") (pintype "passive"))
      (node (ref "U1") (pin "64") (pinfunction "PE11/FSMC_D8_64") (pintype "passive"))
    )
    (net (code "27") (name "/INPUT13") (class "Default")
      (node (ref "P11") (pin "16") (pinfunction "16_16") (pintype "passive"))
      (node (ref "U1") (pin "65") (pinfunction "PE12/FSMC_D9_65") (pintype "passive"))
    )
    (net (code "28") (name "/INPUT14") (class "Default")
      (node (ref "P11") (pin "14") (pinfunction "14_14") (pintype "passive"))
      (node (ref "U1") (pin "66") (pinfunction "PE13/FSMC_D10_66") (pintype "passive"))
    )
    (net (code "29") (name "/INPUT15") (class "Default")
      (node (ref "P11") (pin "12") (pinfunction "12_12") (pintype "passive"))
      (node (ref "U1") (pin "67") (pinfunction "PE14/FSMC_D11_67") (pintype "passive"))
    )
    (net (code "30") (name "/INPUT16") (class "Default")
      (node (ref "P11") (pin "10") (pinfunction "10_10") (pintype "passive"))
      (node (ref "U1") (pin "68") (pinfunction "PE15/FSMC_D12_68") (pintype "passive"))
    )
    (net (code "31") (name "/JTCK") (class "Default")
      (node (ref "R43") (pin "2") (pinfunction "2_2") (pintype "passive"))
      (node (ref "U1") (pin "109") (pinfunction "PA14/JTCK_SWCLK_109") (pintype "passive"))
      (node (ref "U9") (pin "9") (pinfunction "TCK/SWCLK_9") (pintype "passive"))
    )
    (net (code "32") (name "/JTDI") (class "Default")
      (node (ref "R40") (pin "2") (pinfunction "2_2") (pintype "passive"))
      (node (ref "U1") (pin "110") (pinfunction "PA15/JTDI/SPI3_NSS/I2S3_WS_110") (pintype "passive"))
      (node (ref "U9") (pin "5") (pinfunction "TDI_5") (pintype "passive"))
    )
    (net (code "33") (name "/JTDO") (class "Default")
      (node (ref "R42") (pin "2") (pinfunction "2_2") (pintype "passive"))
      (node (ref "U1") (pin "133") (pinfunction "PB3/JTDO/TRACESWO/SPI3_SCK/I2S3_CK_133") (pintype "passive"))
      (node (ref "U9") (pin "13") (pinfunction "TDO/SWO_13") (pintype "passive"))
    )
    (net (code "34") (name "/JTMS") (class "Default")
      (node (ref "R41") (pin "2") (pinfunction "2_2") (pintype "passive"))
      (node (ref "U1") (pin "105") (pinfunction "PA13/JTMS_SWDIO_105") (pintype "passive"))
      (node (ref "U9") (pin "7") (pinfunction "TMS/SWDIO_7") (pintype "passive"))
    )
    (net (code "35") (name "/JTRST") (class "Default")
      (node (ref "R38") (pin "2") (pinfunction "2_2") (pintype "passive"))
      (node (ref "U1") (pin "134") (pinfunction "PB4/JNTRST/SPI3_MISO_134") (pintype "passive"))
      (node (ref "U9") (pin "3") (pinfunction "TRST_3") (pintype "passive"))
    )
    (net (code "36") (name "/KEY_LINE0") (class "Default")
      (node (ref "P2") (pin "1") (pinfunction "1_1") (pintype "passive"))
      (node (ref "U1") (pin "26") (pinfunction "PC0/ADC123_IN10_26") (pintype "passive"))
    )
    (net (code "37") (name "/KEY_LINE1") (class "Default")
      (node (ref "P2") (pin "3") (pinfunction "3_3") (pintype "passive"))
      (node (ref "U1") (pin "27") (pinfunction "PC1/ADC123_IN11_27") (pintype "passive"))
    )
    (net (code "38") (name "/KEY_LINE2") (class "Default")
      (node (ref "P2") (pin "5") (pinfunction "5_5") (pintype "passive"))
      (node (ref "U1") (pin "28") (pinfunction "PC2/ADC123_IN12_28") (pintype "passive"))
    )
    (net (code "39") (name "/KEY_LINE3") (class "Default")
      (node (ref "P2") (pin "7") (pinfunction "7_7") (pintype "passive"))
      (node (ref "U1") (pin "29") (pinfunction "PC3/ADC123_IN13_29") (pintype "passive"))
    )
    (net (code "40") (name "/KEY_ROW0") (class "Default")
      (node (ref "P2") (pin "2") (pinfunction "2_2") (pintype "passive"))
      (node (ref "U1") (pin "44") (pinfunction "PC4/ADC12_IN14_44") (pintype "passive"))
    )
    (net (code "41") (name "/KEY_ROW1") (class "Default")
      (node (ref "P2") (pin "4") (pinfunction "4_4") (pintype "passive"))
      (node (ref "U1") (pin "45") (pinfunction "PC5/ADC12_IN15_45") (pintype "passive"))
    )
    (net (code "42") (name "/KEY_ROW2") (class "Default")
      (node (ref "P2") (pin "6") (pinfunction "6_6") (pintype "passive"))
      (node (ref "U1") (pin "96") (pinfunction "PC6/I2S2_MCK/TIM8_CH1/SDIO_D6_96") (pintype "passive"))
    )
    (net (code "43") (name "/KEY_ROW3") (class "Default")
      (node (ref "P2") (pin "8") (pinfunction "8_8") (pintype "passive"))
      (node (ref "U1") (pin "97") (pinfunction "PC7/I2S3_MCK/TIM8_CH2/SDIO_D7_97") (pintype "passive"))
    )
    (net (code "44") (name "/LCD_CS") (class "Default")
      (node (ref "P2") (pin "10") (pinfunction "10_10") (pintype "passive"))
      (node (ref "R4") (pin "1") (pinfunction "1_1") (pintype "passive"))
      (node (ref "U1") (pin "137") (pinfunction "PB7/I2C1_SDA/FSMC_NADV/TIM4_CH2_137") (pintype "passive"))
    )
    (net (code "45") (name "/LCD_SCK") (class "Default")
      (node (ref "P2") (pin "12") (pinfunction "12_12") (pintype "passive"))
      (node (ref "R6") (pin "1") (pinfunction "1_1") (pintype "passive"))
      (node (ref "U1") (pin "140") (pinfunction "PB9/TIM4_CH4/SDIO_D5_140") (pintype "passive"))
    )
    (net (code "46") (name "/LCD_SDI") (class "Default")
      (node (ref "P2") (pin "14") (pinfunction "14_14") (pintype "passive"))
      (node (ref "R8") (pin "1") (pinfunction "1_1") (pintype "passive"))
      (node (ref "U1") (pin "139") (pinfunction "PB8/TIM4_CH3/SDIO_D4_139") (pintype "passive"))
    )
    (net (code "47") (name "/LED0") (class "Default")
      (node (ref "R9") (pin "2") (pinfunction "2_2") (pintype "passive"))
      (node (ref "U1") (pin "73") (pinfunction "PB12/SPI2_NSS/I2S2_WS/I2C2_SMBAI/USART3_CK/TIM1BKIN_73") (pintype "passive"))
    )
    (net (code "48") (name "/LED1") (class "Default")
      (node (ref "R10") (pin "2") (pinfunction "2_2") (pintype "passive"))
      (node (ref "U1") (pin "74") (pinfunction "PB13/SPI2_SCK/I2S2_CK/USART3_CTS/TIM1_CH1N_74") (pintype "passive"))
    )
    (net (code "49") (name "/LED2") (class "Default")
      (node (ref "R11") (pin "2") (pinfunction "2_2") (pintype "passive"))
      (node (ref "U1") (pin "75") (pinfunction "PB14/SPI2_MISO/USART3_RTS/TIM1_CH2N_75") (pintype "passive"))
    )
    (net (code "50") (name "/LED3") (class "Default")
      (node (ref "R12") (pin "2") (pinfunction "2_2") (pintype "passive"))
      (node (ref "U1") (pin "76") (pinfunction "PB15/SPI2_MOSI/I2S2_SD/TIM1_CH3N_76") (pintype "passive"))
    )
    (net (code "51") (name "/OUTPUT1") (class "Default")
      (node (ref "P13") (pin "1") (pinfunction "1_1") (pintype "passive"))
      (node (ref "U1") (pin "10") (pinfunction "PF0/FSMC_A0_10") (pintype "passive"))
    )
    (net (code "52") (name "/OUTPUT2") (class "Default")
      (node (ref "P13") (pin "3") (pinfunction "3_3") (pintype "passive"))
      (node (ref "U1") (pin "11") (pinfunction "PF1/FSMC_A1_11") (pintype "passive"))
    )
    (net (code "53") (name "/OUTPUT3") (class "Default")
      (node (ref "P13") (pin "5") (pinfunction "5_5") (pintype "passive"))
      (node (ref "U1") (pin "12") (pinfunction "PF2/FSMC_A2_12") (pintype "passive"))
    )
    (net (code "54") (name "/OUTPUT4") (class "Default")
      (node (ref "P13") (pin "7") (pinfunction "7_7") (pintype "passive"))
      (node (ref "U1") (pin "13") (pinfunction "PF3/FSMC_A3_13") (pintype "passive"))
    )
    (net (code "55") (name "/OUTPUT5") (class "Default")
      (node (ref "P13") (pin "9") (pinfunction "9_9") (pintype "passive"))
      (node (ref "U1") (pin "14") (pinfunction "PF4/FSMC_A4_14") (pintype "passive"))
    )
    (net (code "56") (name "/OUTPUT6") (class "Default")
      (node (ref "P13") (pin "10") (pinfunction "10_10") (pintype "passive"))
      (node (ref "U1") (pin "15") (pinfunction "PF5/FSMC_A5_15") (pintype "passive"))
    )
    (net (code "57") (name "/OUTPUT7") (class "Default")
      (node (ref "P13") (pin "8") (pinfunction "8_8") (pintype "passive"))
      (node (ref "U1") (pin "18") (pinfunction "PF6/ADC3_IN4/FSMC_NIORD_18") (pintype "passive"))
    )
    (net (code "58") (name "/OUTPUT8") (class "Default")
      (node (ref "P13") (pin "6") (pinfunction "6_6") (pintype "passive"))
      (node (ref "U1") (pin "19") (pinfunction "PF7/ADC3_IN5/FSMC_NREG_19") (pintype "passive"))
    )
    (net (code "59") (name "/PA2") (class "Default")
      (node (ref "U1") (pin "36") (pinfunction "PA2/USART2_TX/ADC123_IN2/TIM5_CH3/TIM2_CH3_36") (pintype "passive"))
      (node (ref "U6") (pin "11") (pinfunction "T1IN_11") (pintype "passive"))
    )
    (net (code "60") (name "/PA3") (class "Default")
      (node (ref "U1") (pin "37") (pinfunction "PA3/USART2_RX/ADC123_IN3/TIM5_CH4/TIM2_CH4_37") (pintype "passive"))
      (node (ref "U6") (pin "12") (pinfunction "R1OUT_12") (pintype "passive"))
    )
    (net (code "61") (name "/PA4") (class "Default")
      (node (ref "P14") (pin "2") (pinfunction "2_2") (pintype "passive"))
      (node (ref "U1") (pin "40") (pinfunction "PA4/SPI1_NSS/DAC_OUT1/USART2_CK/ADC12_IN4_40") (pintype "passive"))
    )
    (net (code "62") (name "/PA5") (class "Default")
      (node (ref "P14") (pin "1") (pinfunction "1_1") (pintype "passive"))
      (node (ref "P16") (pin "1") (pinfunction "1_1") (pintype "passive"))
      (node (ref "P17") (pin "1") (pinfunction "1_1") (pintype "passive"))
      (node (ref "R35") (pin "1") (pinfunction "1_1") (pintype "passive"))
      (node (ref "U1") (pin "41") (pinfunction "PA5/SPI_SCK/DAC_OUT2/ADC12_IN5_41") (pintype "passive"))
    )
    (net (code "63") (name "/PA6") (class "Default")
      (node (ref "P14") (pin "3") (pinfunction "3_3") (pintype "passive"))
      (node (ref "P16") (pin "3") (pinfunction "3_3") (pintype "passive"))
      (node (ref "P17") (pin "3") (pinfunction "3_3") (pintype "passive"))
      (node (ref "R36") (pin "1") (pinfunction "1_1") (pintype "passive"))
      (node (ref "U1") (pin "42") (pinfunction "PA6/SPI1_MISO/TIM8_BKIN/ADC12_IN6/TIM3_CH1_42") (pintype "passive"))
    )
    (net (code "64") (name "/PA7") (class "Default")
      (node (ref "P14") (pin "5") (pinfunction "5_5") (pintype "passive"))
      (node (ref "P16") (pin "5") (pinfunction "5_5") (pintype "passive"))
      (node (ref "P17") (pin "5") (pinfunction "5_5") (pintype "passive"))
      (node (ref "R39") (pin "1") (pinfunction "1_1") (pintype "passive"))
      (node (ref "U1") (pin "43") (pinfunction "PA7/SPI1_MOSI/TIM8_CH1N/ADC12_IN7/TIM3_CH2_43") (pintype "passive"))
    )
    (net (code "65") (name "/PA8") (class "Default")
      (node (ref "P16") (pin "2") (pinfunction "2_2") (pintype "passive"))
      (node (ref "U1") (pin "100") (pinfunction "PA8/USART1_CK/TIM1_CH1/MCO_100") (pintype "passive"))
    )
    (net (code "66") (name "/PA9") (class "Default")
      (node (ref "U1") (pin "101") (pinfunction "PA9/USART1_TX/TIM1_CH2_101") (pintype "passive"))
      (node (ref "U3") (pin "5") (pinfunction "RXD_5") (pintype "passive"))
    )
    (net (code "67") (name "/PA10") (class "Default")
      (node (ref "U1") (pin "102") (pinfunction "PA10/USART1_RX/TIM1_CH3_102") (pintype "passive"))
      (node (ref "U3") (pin "1") (pinfunction "TXD_1") (pintype "passive"))
    )
    (net (code "68") (name "/PA11") (class "Default")
      (node (ref "P17") (pin "2") (pinfunction "2_2") (pintype "passive"))
      (node (ref "U1") (pin "103") (pinfunction "PA11/USART1_CTS/CAN_RX/TIM1_CH4/USBDM_103") (pintype "passive"))
    )
    (net (code "69") (name "/PA12") (class "Default")
      (node (ref "U1") (pin "104") (pinfunction "PA12/USART1_RTS/CAN_TX/TIM1_ETR/USBDP_104") (pintype "passive"))
    )
    (net (code "70") (name "/PB1") (class "Default")
      (node (ref "P7") (pin "6") (pinfunction "6_6") (pintype "passive"))
      (node (ref "U1") (pin "47") (pinfunction "PB1/ADC12_IN9/TIM3_CH4/TIM8_CH3N_47") (pintype "passive"))
    )
    (net (code "71") (name "/PB5") (class "Default")
      (node (ref "U1") (pin "135") (pinfunction "PB5/I2C1_SMBAI/SPI3_MOSI/I2S3_SD_135") (pintype "passive"))
      (node (ref "U2") (pin "5") (pinfunction "485_CON_5") (pintype "passive"))
    )
    (net (code "72") (name "/PB6") (class "Default")
      (node (ref "U1") (pin "136") (pinfunction "PB6/I2C1_SCL/TIM4_CH1_136") (pintype "passive"))
      (node (ref "U4") (pin "5") (pinfunction "485_CON_5") (pintype "passive"))
    )
    (net (code "73") (name "/PB10") (class "Default")
      (node (ref "U1") (pin "69") (pinfunction "PB10/I2C2_SCL/USART3_TX_69") (pintype "passive"))
      (node (ref "U6") (pin "10") (pinfunction "T2IN_10") (pintype "passive"))
    )
    (net (code "74") (name "/PB11") (class "Default")
      (node (ref "U1") (pin "70") (pinfunction "PB11/I2C2_SDA/USART3_RX_70") (pintype "passive"))
      (node (ref "U6") (pin "9") (pinfunction "R2OUT_9") (pintype "passive"))
    )
    (net (code "75") (name "/PC10") (class "Default")
      (node (ref "U1") (pin "111") (pinfunction "PC10/USART4_TX/SDIO_D2_111") (pintype "passive"))
      (node (ref "U2") (pin "3") (pinfunction "TXD_3") (pintype "passive"))
    )
    (net (code "76") (name "/PC11") (class "Default")
      (node (ref "U1") (pin "112") (pinfunction "PC11/USART4_RX/SDIO_D3_112") (pintype "passive"))
      (node (ref "U2") (pin "4") (pinfunction "RXD_4") (pintype "passive"))
    )
    (net (code "77") (name "/PC12") (class "Default")
      (node (ref "U1") (pin "113") (pinfunction "PC12/USART5_TX/SDIO_CK_113") (pintype "passive"))
      (node (ref "U4") (pin "3") (pinfunction "TXD_3") (pintype "passive"))
    )
    (net (code "78") (name "/PC13") (class "Default")
      (node (ref "P7") (pin "7") (pinfunction "7_7") (pintype "passive"))
      (node (ref "U1") (pin "7") (pinfunction "PC13-TAMPER-RTC_7") (pintype "passive"))
    )
    (net (code "79") (name "/PD0") (class "Default")
      (node (ref "P10") (pin "1") (pinfunction "1_1") (pintype "passive"))
      (node (ref "U1") (pin "114") (pinfunction "PD0/FSMC_D2_114") (pintype "passive"))
    )
    (net (code "80") (name "/PD1") (class "Default")
      (node (ref "P10") (pin "2") (pinfunction "2_2") (pintype "passive"))
      (node (ref "U1") (pin "115") (pinfunction "PD1/FSMC_D3_115") (pintype "passive"))
    )
    (net (code "81") (name "/PD2") (class "Default")
      (node (ref "U1") (pin "116") (pinfunction "PD2/TIM3_ETR/USART5_RX/SDIO_CMD_116") (pintype "passive"))
      (node (ref "U4") (pin "4") (pinfunction "RXD_4") (pintype "passive"))
    )
    (net (code "82") (name "/PD3") (class "Default")
      (node (ref "P10") (pin "4") (pinfunction "4_4") (pintype "passive"))
      (node (ref "U1") (pin "117") (pinfunction "PD3/FSMC_CLK_117") (pintype "passive"))
    )
    (net (code "83") (name "/PD4") (class "Default")
      (node (ref "P10") (pin "5") (pinfunction "5_5") (pintype "passive"))
      (node (ref "U1") (pin "118") (pinfunction "PD4/FSMC_NOE_118") (pintype "passive"))
    )
    (net (code "84") (name "/PD5") (class "Default")
      (node (ref "P10") (pin "6") (pinfunction "6_6") (pintype "passive"))
      (node (ref "U1") (pin "119") (pinfunction "PD5/FSMC_NWE_119") (pintype "passive"))
    )
    (net (code "85") (name "/PD6") (class "Default")
      (node (ref "P10") (pin "7") (pinfunction "7_7") (pintype "passive"))
      (node (ref "U1") (pin "122") (pinfunction "PD6/FSMC_NWAIT_122") (pintype "passive"))
    )
    (net (code "86") (name "/PD7") (class "Default")
      (node (ref "P10") (pin "8") (pinfunction "8_8") (pintype "passive"))
      (node (ref "U1") (pin "123") (pinfunction "PD7/FSMC_NE1/FSMC_NCE2_123") (pintype "passive"))
    )
    (net (code "87") (name "/PD8") (class "Default")
      (node (ref "P10") (pin "9") (pinfunction "9_9") (pintype "passive"))
      (node (ref "U1") (pin "77") (pinfunction "PD8/FSMC_D13_77") (pintype "passive"))
    )
    (net (code "88") (name "/PD9") (class "Default")
      (node (ref "P10") (pin "10") (pinfunction "10_10") (pintype "passive"))
      (node (ref "U1") (pin "78") (pinfunction "PD9/FSMC_D14_78") (pintype "passive"))
    )
    (net (code "89") (name "/PD10") (class "Default")
      (node (ref "P10") (pin "11") (pinfunction "11_11") (pintype "passive"))
      (node (ref "U1") (pin "79") (pinfunction "PD10/FSMC_D15_79") (pintype "passive"))
    )
    (net (code "90") (name "/PD11") (class "Default")
      (node (ref "P10") (pin "12") (pinfunction "12_12") (pintype "passive"))
      (node (ref "U1") (pin "80") (pinfunction "PD11/FSMC_A16_80") (pintype "passive"))
    )
    (net (code "91") (name "/PD12") (class "Default")
      (node (ref "P10") (pin "13") (pinfunction "13_13") (pintype "passive"))
      (node (ref "U1") (pin "81") (pinfunction "PD12/FSMC_A17_81") (pintype "passive"))
    )
    (net (code "92") (name "/PD13") (class "Default")
      (node (ref "P10") (pin "14") (pinfunction "14_14") (pintype "passive"))
      (node (ref "U1") (pin "82") (pinfunction "PD13/FSMC_A18_82") (pintype "passive"))
    )
    (net (code "93") (name "/PD14") (class "Default")
      (node (ref "P7") (pin "13") (pinfunction "13_13") (pintype "passive"))
      (node (ref "U1") (pin "85") (pinfunction "PD14/FSMC_D0_85") (pintype "passive"))
    )
    (net (code "94") (name "/PD15") (class "Default")
      (node (ref "P7") (pin "14") (pinfunction "14_14") (pintype "passive"))
      (node (ref "U1") (pin "86") (pinfunction "PD15/FSMC_D1_86") (pintype "passive"))
    )
    (net (code "95") (name "/PF8") (class "Default")
      (node (ref "P7") (pin "1") (pinfunction "1_1") (pintype "passive"))
      (node (ref "U1") (pin "20") (pinfunction "PF8/ADC3_IN6/FSMC_NIOWR_20") (pintype "passive"))
    )
    (net (code "96") (name "/PF9") (class "Default")
      (node (ref "P7") (pin "2") (pinfunction "2_2") (pintype "passive"))
      (node (ref "U1") (pin "21") (pinfunction "PF9/ADC3_IN7/FSMC_CD_21") (pintype "passive"))
    )
    (net (code "97") (name "/PF10") (class "Default")
      (node (ref "P7") (pin "3") (pinfunction "3_3") (pintype "passive"))
      (node (ref "U1") (pin "22") (pinfunction "PF10/ADC3_IN8/FSMC_INTR_22") (pintype "passive"))
    )
    (net (code "98") (name "/PF11") (class "Default")
      (node (ref "P7") (pin "4") (pinfunction "4_4") (pintype "passive"))
      (node (ref "U1") (pin "49") (pinfunction "PF11/FSMC_NIOS16_49") (pintype "passive"))
    )
    (net (code "99") (name "/PF12") (class "Default")
      (node (ref "P7") (pin "5") (pinfunction "5_5") (pintype "passive"))
      (node (ref "U1") (pin "50") (pinfunction "PF12/FSMC_A6_50") (pintype "passive"))
    )
    (net (code "100") (name "/PF13") (class "Default")
      (node (ref "P7") (pin "8") (pinfunction "8_8") (pintype "passive"))
      (node (ref "U1") (pin "53") (pinfunction "PF13/FSMC_A7_53") (pintype "passive"))
    )
    (net (code "101") (name "/PF14") (class "Default")
      (node (ref "P7") (pin "9") (pinfunction "9_9") (pintype "passive"))
      (node (ref "U1") (pin "54") (pinfunction "PF14/FSMC_A8_54") (pintype "passive"))
    )
    (net (code "102") (name "/PF15") (class "Default")
      (node (ref "P7") (pin "10") (pinfunction "10_10") (pintype "passive"))
      (node (ref "U1") (pin "55") (pinfunction "PF15/FSMC_A9_55") (pintype "passive"))
    )
    (net (code "103") (name "/PG0") (class "Default")
      (node (ref "P1") (pin "1") (pinfunction "1_1") (pintype "passive"))
      (node (ref "U1") (pin "56") (pinfunction "PG0/FSMC_A10_56") (pintype "passive"))
    )
    (net (code "104") (name "/PG1") (class "Default")
      (node (ref "P1") (pin "2") (pinfunction "2_2") (pintype "passive"))
      (node (ref "U1") (pin "57") (pinfunction "PG1/FSMC_A11_57") (pintype "passive"))
    )
    (net (code "105") (name "/PG2") (class "Default")
      (node (ref "P1") (pin "3") (pinfunction "3_3") (pintype "passive"))
      (node (ref "U1") (pin "87") (pinfunction "PG2/FSMC_A12_87") (pintype "passive"))
    )
    (net (code "106") (name "/PG3") (class "Default")
      (node (ref "P1") (pin "4") (pinfunction "4_4") (pintype "passive"))
      (node (ref "U1") (pin "88") (pinfunction "PG3/FSMC_A13_88") (pintype "passive"))
    )
    (net (code "107") (name "/PG4") (class "Default")
      (node (ref "P1") (pin "5") (pinfunction "5_5") (pintype "passive"))
      (node (ref "U1") (pin "89") (pinfunction "PG4/FSMC_A14_89") (pintype "passive"))
    )
    (net (code "108") (name "/PG5") (class "Default")
      (node (ref "P1") (pin "6") (pinfunction "6_6") (pintype "passive"))
      (node (ref "U1") (pin "90") (pinfunction "PG5/FSMC_A15_90") (pintype "passive"))
    )
    (net (code "109") (name "/PG6") (class "Default")
      (node (ref "P1") (pin "7") (pinfunction "7_7") (pintype "passive"))
      (node (ref "U1") (pin "91") (pinfunction "PG6/FSMC_INT2_91") (pintype "passive"))
    )
    (net (code "110") (name "/PG7") (class "Default")
      (node (ref "P1") (pin "8") (pinfunction "8_8") (pintype "passive"))
      (node (ref "U1") (pin "92") (pinfunction "PG7/FSMC_INT3_92") (pintype "passive"))
    )
    (net (code "111") (name "/PG8") (class "Default")
      (node (ref "P1") (pin "9") (pinfunction "9_9") (pintype "passive"))
      (node (ref "U1") (pin "93") (pinfunction "PG8_93") (pintype "passive"))
    )
    (net (code "112") (name "/PG9") (class "Default")
      (node (ref "P1") (pin "10") (pinfunction "10_10") (pintype "passive"))
      (node (ref "U1") (pin "124") (pinfunction "PG9/FSMC_NE2/FSMC_NCE3_124") (pintype "passive"))
    )
    (net (code "113") (name "/PG10") (class "Default")
      (node (ref "P1") (pin "11") (pinfunction "11_11") (pintype "passive"))
      (node (ref "U1") (pin "125") (pinfunction "PG10/FSMC_NCE4_1/FSMC_NE3_125") (pintype "passive"))
    )
    (net (code "114") (name "/PG11") (class "Default")
      (node (ref "P1") (pin "12") (pinfunction "12_12") (pintype "passive"))
      (node (ref "U1") (pin "126") (pinfunction "PG11/FSMC_NCE4_2_126") (pintype "passive"))
    )
    (net (code "115") (name "/PG12") (class "Default")
      (node (ref "P1") (pin "13") (pinfunction "13_13") (pintype "passive"))
      (node (ref "U1") (pin "127") (pinfunction "PG12/FSMC_NE4_127") (pintype "passive"))
    )
    (net (code "116") (name "/PG13") (class "Default")
      (node (ref "P1") (pin "14") (pinfunction "14_14") (pintype "passive"))
      (node (ref "U1") (pin "128") (pinfunction "PG13/FSMC_A24_128") (pintype "passive"))
    )
    (net (code "117") (name "/PG14") (class "Default")
      (node (ref "P7") (pin "11") (pinfunction "11_11") (pintype "passive"))
      (node (ref "U1") (pin "129") (pinfunction "PG14/FSMC_A25_129") (pintype "passive"))
    )
    (net (code "118") (name "/PG15") (class "Default")
      (node (ref "P7") (pin "12") (pinfunction "12_12") (pintype "passive"))
      (node (ref "U1") (pin "132") (pinfunction "PG15_132") (pintype "passive"))
    )
    (net (code "119") (name "/PL2303D+") (class "Default")
      (node (ref "R18") (pin "1") (pinfunction "1_1") (pintype "passive"))
      (node (ref "U3") (pin "15") (pinfunction "DP_15") (pintype "passive"))
    )
    (net (code "120") (name "/PL2303D-") (class "Default")
      (node (ref "R16") (pin "1") (pinfunction "1_1") (pintype "passive"))
      (node (ref "U3") (pin "16") (pinfunction "DM_16") (pintype "passive"))
    )
    (net (code "121") (name "/REST") (class "Default")
      (node (ref "C6") (pin "1") (pinfunction "1_1") (pintype "passive"))
      (node (ref "D1") (pin "1") (pinfunction "A_1") (pintype "passive"))
      (node (ref "K_RST1") (pin "1") (pinfunction "1_1") (pintype "passive"))
      (node (ref "R22") (pin "1") (pinfunction "1_1") (pintype "passive"))
      (node (ref "U1") (pin "25") (pinfunction "NRST_25") (pintype "passive"))
      (node (ref "U9") (pin "15") (pinfunction "RST_15") (pintype "passive"))
    )
    (net (code "122") (name "/RS232_2_RX") (class "Default")
      (node (ref "J2") (pin "3") (pinfunction "3_3") (pintype "passive"))
      (node (ref "P15") (pin "4") (pinfunction "4_4") (pintype "passive"))
      (node (ref "U6") (pin "13") (pinfunction "R1IN_13") (pintype "passive"))
    )
    (net (code "123") (name "/RS232_2_TX") (class "Default")
      (node (ref "J2") (pin "2") (pinfunction "2_2") (pintype "passive"))
      (node (ref "P15") (pin "3") (pinfunction "3_3") (pintype "passive"))
      (node (ref "U6") (pin "14") (pinfunction "T1OUT_14") (pintype "passive"))
    )
    (net (code "124") (name "/RS232_3_RX") (class "Default")
      (node (ref "J1") (pin "3") (pinfunction "3_3") (pintype "passive"))
      (node (ref "U6") (pin "8") (pinfunction "R2IN_8") (pintype "passive"))
    )
    (net (code "125") (name "/RS232_3_TX") (class "Default")
      (node (ref "J1") (pin "2") (pinfunction "2_2") (pintype "passive"))
      (node (ref "U6") (pin "7") (pinfunction "T2OUT_7") (pintype "passive"))
    )
    (net (code "126") (name "/VBAT") (class "Default")
      (node (ref "D6") (pin "2") (pinfunction "K_2") (pintype "passive"))
      (node (ref "D7") (pin "2") (pinfunction "K_2") (pintype "passive"))
      (node (ref "U1") (pin "6") (pinfunction "VBAT_6") (pintype "passive"))
    )
    (net (code "127") (name "/VDDA") (class "Default")
      (node (ref "C21") (pin "2") (pinfunction "2_2") (pintype "passive"))
      (node (ref "C22") (pin "1") (pinfunction "1_1") (pintype "passive"))
      (node (ref "L1") (pin "1") (pinfunction "1_1") (pintype "passive"))
      (node (ref "R30") (pin "2") (pinfunction "2_2") (pintype "passive"))
      (node (ref "U1") (pin "33") (pinfunction "VDDA_33") (pintype "passive"))
    )
    (net (code "128") (name "GND") (class "Default")
      (node (ref "BAT1") (pin "2") (pinfunction "-_2") (pintype "passive"))
      (node (ref "C1") (pin "1") (pinfunction "1_1") (pintype "passive"))
      (node (ref "C10") (pin "2") (pinfunction "2_2") (pintype "passive"))
      (node (ref "C12") (pin "1") (pinfunction "1_1") (pintype "passive"))
      (node (ref "C13") (pin "2") (pinfunction "2_2") (pintype "passive"))
      (node (ref "C14") (pin "1") (pinfunction "1_1") (pintype "passive"))
      (node (ref "C15") (pin "2") (pinfunction "2_2") (pintype "passive"))
      (node (ref "C16") (pin "1") (pinfunction "1_1") (pintype "passive"))
      (node (ref "C17") (pin "2") (pinfunction "2_2") (pintype "passive"))
      (node (ref "C18") (pin "1") (pinfunction "1_1") (pintype "passive"))
      (node (ref "C19") (pin "1") (pinfunction "1_1") (pintype "passive"))
      (node (ref "C2") (pin "1") (pinfunction "1_1") (pintype "passive"))
      (node (ref "C20") (pin "1") (pinfunction "1_1") (pintype "passive"))
      (node (ref "C21") (pin "1") (pinfunction "1_1") (pintype "passive"))
      (node (ref "C22") (pin "2") (pinfunction "2_2") (pintype "passive"))
      (node (ref "C23") (pin "1") (pinfunction "1_1") (pintype "passive"))
      (node (ref "C24") (pin "1") (pinfunction "1_1") (pintype "passive"))
      (node (ref "C25") (pin "1") (pinfunction "1_1") (pintype "passive"))
      (node (ref "C26") (pin "1") (pinfunction "1_1") (pintype "passive"))
      (node (ref "C27") (pin "1") (pinfunction "1_1") (pintype "passive"))
      (node (ref "C28") (pin "1") (pinfunction "1_1") (pintype "passive"))
      (node (ref "C29") (pin "1") (pinfunction "1_1") (pintype "passive"))
      (node (ref "C3") (pin "1") (pinfunction "1_1") (pintype "passive"))
      (node (ref "C30") (pin "1") (pinfunction "1_1") (pintype "passive"))
      (node (ref "C31") (pin "1") (pinfunction "1_1") (pintype "passive"))
      (node (ref "C32") (pin "1") (pinfunction "1_1") (pintype "passive"))
      (node (ref "C33") (pin "1") (pinfunction "1_1") (pintype "passive"))
      (node (ref "C34") (pin "1") (pinfunction "1_1") (pintype "passive"))
      (node (ref "C4") (pin "1") (pinfunction "1_1") (pintype "passive"))
      (node (ref "C5") (pin "2") (pinfunction "2_2") (pintype "passive"))
      (node (ref "C6") (pin "2") (pinfunction "2_2") (pintype "passive"))
      (node (ref "C9") (pin "2") (pinfunction "2_2") (pintype "passive"))
      (node (ref "D2") (pin "2") (pinfunction "K_2") (pintype "passive"))
      (node (ref "D3") (pin "2") (pinfunction "K_2") (pintype "passive"))
      (node (ref "D4") (pin "2") (pinfunction "K_2") (pintype "passive"))
      (node (ref "D5") (pin "2") (pinfunction "K_2") (pintype "passive"))
      (node (ref "D8") (pin "2") (pinfunction "K_2") (pintype "passive"))
      (node (ref "J1") (pin "5") (pinfunction "5_5") (pintype "passive"))
      (node (ref "J2") (pin "5") (pinfunction "5_5") (pintype "passive"))
      (node (ref "K_RST1") (pin "2") (pinfunction "2_2") (pintype "passive"))
      (node (ref "LS1") (pin "2") (pinfunction "B_2") (pintype "passive"))
      (node (ref "P12") (pin "5") (pinfunction "5_5") (pintype "passive"))
      (node (ref "P12") (pin "6") (pinfunction "6_6") (pintype "passive"))
      (node (ref "P14") (pin "7") (pinfunction "7_7") (pintype "passive"))
      (node (ref "P15") (pin "2") (pinfunction "2_2") (pintype "passive"))
      (node (ref "P16") (pin "7") (pinfunction "7_7") (pintype "passive"))
      (node (ref "P17") (pin "7") (pinfunction "7_7") (pintype "passive"))
      (node (ref "P2") (pin "9") (pinfunction "9_9") (pintype "passive"))
      (node (ref "P4") (pin "1") (pinfunction "1_1") (pintype "passive"))
      (node (ref "P4") (pin "2") (pinfunction "2_2") (pintype "passive"))
      (node (ref "P4") (pin "3") (pinfunction "3_3") (pintype "passive"))
      (node (ref "P4") (pin "4") (pinfunction "4_4") (pintype "passive"))
      (node (ref "P4") (pin "5") (pinfunction "5_5") (pintype "passive"))
      (node (ref "P4") (pin "6") (pinfunction "6_6") (pintype "passive"))
      (node (ref "R43") (pin "1") (pinfunction "1_1") (pintype "passive"))
      (node (ref "S1") (pin "5") (pinfunction "B2_5") (pintype "passive"))
      (node (ref "U1") (pin "107") (pinfunction "VSS_107") (pintype "passive"))
      (node (ref "U1") (pin "120") (pinfunction "VSS_120") (pintype "passive"))
      (node (ref "U1") (pin "130") (pinfunction "VSS_130") (pintype "passive"))
      (node (ref "U1") (pin "143") (pinfunction "VSS_143") (pintype "passive"))
      (node (ref "U1") (pin "16") (pinfunction "VSS_16") (pintype "passive"))
      (node (ref "U1") (pin "30") (pinfunction "VSSA_30") (pintype "passive"))
      (node (ref "U1") (pin "31") (pinfunction "Vref-_31") (pintype "passive"))
      (node (ref "U1") (pin "38") (pinfunction "VSS_38") (pintype "passive"))
      (node (ref "U1") (pin "51") (pinfunction "VSS_51") (pintype "passive"))
      (node (ref "U1") (pin "61") (pinfunction "VSS_61") (pintype "passive"))
      (node (ref "U1") (pin "71") (pinfunction "VSS_71") (pintype "passive"))
      (node (ref "U1") (pin "83") (pinfunction "VSS_83") (pintype "passive"))
      (node (ref "U1") (pin "94") (pinfunction "VSS_94") (pintype "passive"))
      (node (ref "U2") (pin "2") (pinfunction "GND_2") (pintype "passive"))
      (node (ref "U3") (pin "18") (pinfunction "GND_3V3_18") (pintype "passive"))
      (node (ref "U3") (pin "21") (pinfunction "GND_21") (pintype "passive"))
      (node (ref "U3") (pin "25") (pinfunction "GND_PLL_25") (pintype "passive"))
      (node (ref "U3") (pin "26") (pinfunction "PLL_TEST_26") (pintype "passive"))
      (node (ref "U3") (pin "7") (pinfunction "GND_7") (pintype "passive"))
      (node (ref "U4") (pin "2") (pinfunction "GND_2") (pintype "passive"))
      (node (ref "U6") (pin "15") (pinfunction "GND_15") (pintype "passive"))
      (node (ref "U7") (pin "1") (pinfunction "GND_1") (pintype "passive"))
      (node (ref "U8") (pin "1") (pinfunction "E0_1") (pintype "input"))
      (node (ref "U8") (pin "2") (pinfunction "E1_2") (pintype "input"))
      (node (ref "U8") (pin "3") (pinfunction "E2_3") (pintype "input"))
      (node (ref "U8") (pin "4") (pinfunction "GND_4") (pintype "power_in"))
      (node (ref "U8") (pin "7") (pinfunction "MODE_7") (pintype "input"))
      (node (ref "U9") (pin "10") (pinfunction "GND_10") (pintype "passive"))
      (node (ref "U9") (pin "12") (pinfunction "GND_12") (pintype "passive"))
      (node (ref "U9") (pin "14") (pinfunction "GND_14") (pintype "passive"))
      (node (ref "U9") (pin "16") (pinfunction "GND_16") (pintype "passive"))
      (node (ref "U9") (pin "18") (pinfunction "GND_18") (pintype "passive"))
      (node (ref "U9") (pin "20") (pinfunction "GND_20") (pintype "passive"))
      (node (ref "U9") (pin "4") (pinfunction "GND_4") (pintype "passive"))
      (node (ref "U9") (pin "6") (pinfunction "GND_6") (pintype "passive"))
      (node (ref "U9") (pin "8") (pinfunction "GND_8") (pintype "passive"))
    )
    (net (code "129") (name "GNDIN") (class "Default")
      (node (ref "P9") (pin "1") (pinfunction "1_1") (pintype "passive"))
      (node (ref "S1") (pin "6") (pinfunction "B1_6") (pintype "passive"))
      (node (ref "U5") (pin "5") (pinfunction "GND_5") (pintype "passive"))
    )
    (net (code "130") (name "Net-(BAT1-+)") (class "Default")
      (node (ref "BAT1") (pin "1") (pinfunction "+_1") (pintype "passive"))
      (node (ref "D7") (pin "1") (pinfunction "A_1") (pintype "passive"))
    )
    (net (code "131") (name "Net-(D1-K)") (class "Default")
      (node (ref "D1") (pin "2") (pinfunction "K_2") (pintype "passive"))
      (node (ref "Q1") (pin "1") (pinfunction "C_1") (pintype "passive"))
      (node (ref "R1") (pin "1") (pinfunction "1_1") (pintype "passive"))
    )
    (net (code "132") (name "Net-(D2-A)") (class "Default")
      (node (ref "D2") (pin "1") (pinfunction "A_1") (pintype "passive"))
      (node (ref "R9") (pin "1") (pinfunction "1_1") (pintype "passive"))
    )
    (net (code "133") (name "Net-(D3-A)") (class "Default")
      (node (ref "D3") (pin "1") (pinfunction "A_1") (pintype "passive"))
      (node (ref "R10") (pin "1") (pinfunction "1_1") (pintype "passive"))
    )
    (net (code "134") (name "Net-(D4-A)") (class "Default")
      (node (ref "D4") (pin "1") (pinfunction "A_1") (pintype "passive"))
      (node (ref "R11") (pin "1") (pinfunction "1_1") (pintype "passive"))
    )
    (net (code "135") (name "Net-(D5-A)") (class "Default")
      (node (ref "D5") (pin "1") (pinfunction "A_1") (pintype "passive"))
      (node (ref "R12") (pin "1") (pinfunction "1_1") (pintype "passive"))
    )
    (net (code "136") (name "Net-(D8-A)") (class "Default")
      (node (ref "D8") (pin "1") (pinfunction "A_1") (pintype "passive"))
      (node (ref "R27") (pin "2") (pinfunction "2_2") (pintype "passive"))
    )
    (net (code "137") (name "Net-(J1-Pad4)") (class "Default")
      (node (ref "J1") (pin "4") (pinfunction "4_4") (pintype "passive"))
      (node (ref "J1") (pin "6") (pinfunction "6_6") (pintype "passive"))
    )
    (net (code "138") (name "Net-(J1-Pad7)") (class "Default")
      (node (ref "J1") (pin "7") (pinfunction "7_7") (pintype "passive"))
      (node (ref "J1") (pin "8") (pinfunction "8_8") (pintype "passive"))
    )
    (net (code "139") (name "Net-(J2-Pad4)") (class "Default")
      (node (ref "J2") (pin "4") (pinfunction "4_4") (pintype "passive"))
      (node (ref "J2") (pin "6") (pinfunction "6_6") (pintype "passive"))
    )
    (net (code "140") (name "Net-(J2-Pad7)") (class "Default")
      (node (ref "J2") (pin "7") (pinfunction "7_7") (pintype "passive"))
      (node (ref "J2") (pin "8") (pinfunction "8_8") (pintype "passive"))
    )
    (net (code "141") (name "Net-(LS1-A)") (class "Default")
      (node (ref "LS1") (pin "1") (pinfunction "A_1") (pintype "passive"))
      (node (ref "Q3") (pin "1") (pinfunction "C_1") (pintype "passive"))
    )
    (net (code "142") (name "Net-(P12-Pad3)") (class "Default")
      (node (ref "P12") (pin "3") (pinfunction "3_3") (pintype "passive"))
      (node (ref "R20") (pin "2") (pinfunction "2_2") (pintype "passive"))
    )
    (net (code "143") (name "Net-(P12-Pad4)") (class "Default")
      (node (ref "P12") (pin "4") (pinfunction "4_4") (pintype "passive"))
      (node (ref "R21") (pin "1") (pinfunction "1_1") (pintype "passive"))
    )
    (net (code "144") (name "Net-(Q1-B)") (class "Default")
      (node (ref "Q1") (pin "2") (pinfunction "B_2") (pintype "passive"))
      (node (ref "R3") (pin "2") (pinfunction "2_2") (pintype "passive"))
    )
    (net (code "145") (name "Net-(Q1-E)") (class "Default")
      (node (ref "Q1") (pin "3") (pinfunction "E_3") (pintype "passive"))
      (node (ref "R13") (pin "2") (pinfunction "2_2") (pintype "passive"))
      (node (ref "R5") (pin "2") (pinfunction "2_2") (pintype "passive"))
      (node (ref "U3") (pin "3") (pinfunction "RTS_N_3") (pintype "passive"))
    )
    (net (code "146") (name "Net-(Q2-B)") (class "Default")
      (node (ref "Q2") (pin "2") (pinfunction "B_2") (pintype "passive"))
      (node (ref "R13") (pin "1") (pinfunction "1_1") (pintype "passive"))
    )
    (net (code "147") (name "Net-(Q2-C)") (class "Default")
      (node (ref "Q2") (pin "1") (pinfunction "C_1") (pintype "passive"))
      (node (ref "R15") (pin "2") (pinfunction "2_2") (pintype "passive"))
    )
    (net (code "148") (name "Net-(Q3-B)") (class "Default")
      (node (ref "Q3") (pin "2") (pinfunction "B_2") (pintype "passive"))
      (node (ref "R33") (pin "2") (pinfunction "2_2") (pintype "passive"))
    )
    (net (code "149") (name "Net-(U1-OSC_IN)") (class "Default")
      (node (ref "C14") (pin "2") (pinfunction "2_2") (pintype "passive"))
      (node (ref "R28") (pin "1") (pinfunction "1_1") (pintype "passive"))
      (node (ref "U1") (pin "23") (pinfunction "OSC_IN_23") (pintype "passive"))
      (node (ref "Y3") (pin "1") (pinfunction "OSC1_1") (pintype "passive"))
    )
    (net (code "150") (name "Net-(U1-OSC_OUT)") (class "Default")
      (node (ref "C19") (pin "2") (pinfunction "2_2") (pintype "passive"))
      (node (ref "R28") (pin "2") (pinfunction "2_2") (pintype "passive"))
      (node (ref "U1") (pin "24") (pinfunction "OSC_OUT_24") (pintype "passive"))
      (node (ref "Y3") (pin "2") (pinfunction "OSC2_2") (pintype "passive"))
    )
    (net (code "151") (name "Net-(U1-PC14-OSC32_IN)") (class "Default")
      (node (ref "C10") (pin "1") (pinfunction "1_1") (pintype "passive"))
      (node (ref "U1") (pin "8") (pinfunction "PC14-OSC32_IN_8") (pintype "passive"))
      (node (ref "Y2") (pin "2") (pinfunction "OSC2_2") (pintype "passive"))
    )
    (net (code "152") (name "Net-(U1-PC15-OSC32_OUT)") (class "Default")
      (node (ref "R24") (pin "2") (pinfunction "2_2") (pintype "passive"))
      (node (ref "U1") (pin "9") (pinfunction "PC15-OSC32_OUT_9") (pintype "passive"))
    )
    (net (code "153") (name "Net-(U1-Vref+)") (class "Default")
      (node (ref "R30") (pin "1") (pinfunction "1_1") (pintype "passive"))
      (node (ref "U1") (pin "32") (pinfunction "Vref+_32") (pintype "passive"))
    )
    (net (code "154") (name "Net-(U3-DTR_N)") (class "Default")
      (node (ref "R2") (pin "1") (pinfunction "1_1") (pintype "passive"))
      (node (ref "R3") (pin "1") (pinfunction "1_1") (pintype "passive"))
      (node (ref "U3") (pin "2") (pinfunction "DTR_N_2") (pintype "passive"))
    )
    (net (code "155") (name "Net-(U3-LD_MODE)") (class "Default")
      (node (ref "R14") (pin "1") (pinfunction "1_1") (pintype "passive"))
      (node (ref "U3") (pin "22") (pinfunction "TRI_MODE_22") (pintype "passive"))
      (node (ref "U3") (pin "23") (pinfunction "LD_MODE_23") (pintype "passive"))
    )
    (net (code "156") (name "Net-(U3-OSC1)") (class "Default")
      (node (ref "C2") (pin "2") (pinfunction "2_2") (pintype "passive"))
      (node (ref "U3") (pin "27") (pinfunction "OSC1_27") (pintype "passive"))
      (node (ref "Y1") (pin "1") (pinfunction "OSC1_1") (pintype "passive"))
    )
    (net (code "157") (name "Net-(U3-OSC2)") (class "Default")
      (node (ref "C1") (pin "2") (pinfunction "2_2") (pintype "passive"))
      (node (ref "U3") (pin "28") (pinfunction "OSC2_28") (pintype "passive"))
      (node (ref "Y1") (pin "2") (pinfunction "OSC2_2") (pintype "passive"))
    )
    (net (code "158") (name "Net-(U5-D+)") (class "Default")
      (node (ref "R18") (pin "2") (pinfunction "2_2") (pintype "passive"))
      (node (ref "R19") (pin "2") (pinfunction "2_2") (pintype "passive"))
      (node (ref "U5") (pin "3") (pinfunction "D+_3") (pintype "passive"))
    )
    (net (code "159") (name "Net-(U5-D-)") (class "Default")
      (node (ref "R16") (pin "2") (pinfunction "2_2") (pintype "passive"))
      (node (ref "U5") (pin "2") (pinfunction "D-_2") (pintype "passive"))
    )
    (net (code "160") (name "Net-(U6-C1+)") (class "Default")
      (node (ref "C8") (pin "2") (pinfunction "2_2") (pintype "passive"))
      (node (ref "U6") (pin "1") (pinfunction "C1+_1") (pintype "passive"))
    )
    (net (code "161") (name "Net-(U6-C1-)") (class "Default")
      (node (ref "C8") (pin "1") (pinfunction "1_1") (pintype "passive"))
      (node (ref "U6") (pin "3") (pinfunction "C1-_3") (pintype "passive"))
    )
    (net (code "162") (name "Net-(U6-C2+)") (class "Default")
      (node (ref "C11") (pin "2") (pinfunction "2_2") (pintype "passive"))
      (node (ref "U6") (pin "4") (pinfunction "C2+_4") (pintype "passive"))
    )
    (net (code "163") (name "Net-(U6-C2-)") (class "Default")
      (node (ref "C11") (pin "1") (pinfunction "1_1") (pintype "passive"))
      (node (ref "U6") (pin "5") (pinfunction "C2-_5") (pintype "passive"))
    )
    (net (code "164") (name "Net-(U6-V+)") (class "Default")
      (node (ref "C7") (pin "1") (pinfunction "1_1") (pintype "passive"))
      (node (ref "U6") (pin "2") (pinfunction "V+_2") (pintype "passive"))
    )
    (net (code "165") (name "Net-(U6-V-)") (class "Default")
      (node (ref "C12") (pin "2") (pinfunction "2_2") (pintype "passive"))
      (node (ref "U6") (pin "6") (pinfunction "V-_6") (pintype "passive"))
    )
    (net (code "166") (name "Net-(Y2-OSC1)") (class "Default")
      (node (ref "C13") (pin "1") (pinfunction "1_1") (pintype "passive"))
      (node (ref "R24") (pin "1") (pinfunction "1_1") (pintype "passive"))
      (node (ref "Y2") (pin "1") (pinfunction "OSC1_1") (pintype "passive"))
    )
    (net (code "167") (name "VCC") (class "Default")
      (node (ref "C15") (pin "1") (pinfunction "1_1") (pintype "passive"))
      (node (ref "C16") (pin "2") (pinfunction "2_2") (pintype "passive"))
      (node (ref "C4") (pin "2") (pinfunction "2_2") (pintype "passive"))
      (node (ref "P15") (pin "1") (pinfunction "1_1") (pintype "passive"))
      (node (ref "P2") (pin "13") (pinfunction "13_13") (pintype "passive"))
      (node (ref "P5") (pin "1") (pinfunction "1_1") (pintype "passive"))
      (node (ref "P5") (pin "2") (pinfunction "2_2") (pintype "passive"))
      (node (ref "P5") (pin "3") (pinfunction "3_3") (pintype "passive"))
      (node (ref "P5") (pin "4") (pinfunction "4_4") (pintype "passive"))
      (node (ref "P5") (pin "5") (pinfunction "5_5") (pintype "passive"))
      (node (ref "P5") (pin "6") (pinfunction "6_6") (pintype "passive"))
      (node (ref "Q3") (pin "3") (pinfunction "E_3") (pintype "passive"))
      (node (ref "R14") (pin "2") (pinfunction "2_2") (pintype "passive"))
      (node (ref "R4") (pin "2") (pinfunction "2_2") (pintype "passive"))
      (node (ref "R6") (pin "2") (pinfunction "2_2") (pintype "passive"))
      (node (ref "R8") (pin "2") (pinfunction "2_2") (pintype "passive"))
      (node (ref "S1") (pin "2") (pinfunction "A2_2") (pintype "passive"))
      (node (ref "U3") (pin "19") (pinfunction "RESET_19") (pintype "passive"))
      (node (ref "U3") (pin "20") (pinfunction "VDD_20") (pintype "passive"))
      (node (ref "U3") (pin "24") (pinfunction "VDD_PLL_24") (pintype "passive"))
      (node (ref "U3") (pin "8") (pinfunction "VDD_8") (pintype "passive"))
      (node (ref "U7") (pin "3") (pinfunction "IN_3") (pintype "passive"))
    )
    (net (code "168") (name "VCC3.3V") (class "Default")
      (node (ref "C17") (pin "1") (pinfunction "1_1") (pintype "passive"))
      (node (ref "C18") (pin "2") (pinfunction "2_2") (pintype "passive"))
      (node (ref "C20") (pin "2") (pinfunction "2_2") (pintype "passive"))
      (node (ref "C23") (pin "2") (pinfunction "2_2") (pintype "passive"))
      (node (ref "C24") (pin "2") (pinfunction "2_2") (pintype "passive"))
      (node (ref "C25") (pin "2") (pinfunction "2_2") (pintype "passive"))
      (node (ref "C26") (pin "2") (pinfunction "2_2") (pintype "passive"))
      (node (ref "C27") (pin "2") (pinfunction "2_2") (pintype "passive"))
      (node (ref "C28") (pin "2") (pinfunction "2_2") (pintype "passive"))
      (node (ref "C29") (pin "2") (pinfunction "2_2") (pintype "passive"))
      (node (ref "C30") (pin "2") (pinfunction "2_2") (pintype "passive"))
      (node (ref "C31") (pin "2") (pinfunction "2_2") (pintype "passive"))
      (node (ref "C32") (pin "2") (pinfunction "2_2") (pintype "passive"))
      (node (ref "C33") (pin "2") (pinfunction "2_2") (pintype "passive"))
      (node (ref "C34") (pin "2") (pinfunction "2_2") (pintype "passive"))
      (node (ref "C7") (pin "2") (pinfunction "2_2") (pintype "passive"))
      (node (ref "C9") (pin "1") (pinfunction "1_1") (pintype "passive"))
      (node (ref "D6") (pin "1") (pinfunction "A_1") (pintype "passive"))
      (node (ref "L1") (pin "2") (pinfunction "2_2") (pintype "passive"))
      (node (ref "P12") (pin "1") (pinfunction "1_1") (pintype "passive"))
      (node (ref "P12") (pin "2") (pinfunction "2_2") (pintype "passive"))
      (node (ref "P14") (pin "9") (pinfunction "9_9") (pintype "passive"))
      (node (ref "P16") (pin "9") (pinfunction "9_9") (pintype "passive"))
      (node (ref "P17") (pin "9") (pinfunction "9_9") (pintype "passive"))
      (node (ref "P6") (pin "1") (pinfunction "1_1") (pintype "passive"))
      (node (ref "P6") (pin "2") (pinfunction "2_2") (pintype "passive"))
      (node (ref "P6") (pin "3") (pinfunction "3_3") (pintype "passive"))
      (node (ref "P6") (pin "4") (pinfunction "4_4") (pintype "passive"))
      (node (ref "P6") (pin "5") (pinfunction "5_5") (pintype "passive"))
      (node (ref "P6") (pin "6") (pinfunction "6_6") (pintype "passive"))
      (node (ref "Q2") (pin "3") (pinfunction "E_3") (pintype "passive"))
      (node (ref "R1") (pin "2") (pinfunction "2_2") (pintype "passive"))
      (node (ref "R19") (pin "1") (pinfunction "1_1") (pintype "passive"))
      (node (ref "R2") (pin "2") (pinfunction "2_2") (pintype "passive"))
      (node (ref "R22") (pin "2") (pinfunction "2_2") (pintype "passive"))
      (node (ref "R27") (pin "1") (pinfunction "1_1") (pintype "passive"))
      (node (ref "R34") (pin "2") (pinfunction "2_2") (pintype "passive"))
      (node (ref "R35") (pin "2") (pinfunction "2_2") (pintype "passive"))
      (node (ref "R36") (pin "2") (pinfunction "2_2") (pintype "passive"))
      (node (ref "R37") (pin "1") (pinfunction "1_1") (pintype "passive"))
      (node (ref "R38") (pin "1") (pinfunction "1_1") (pintype "passive"))
      (node (ref "R39") (pin "2") (pinfunction "2_2") (pintype "passive"))
      (node (ref "R40") (pin "1") (pinfunction "1_1") (pintype "passive"))
      (node (ref "R41") (pin "1") (pinfunction "1_1") (pintype "passive"))
      (node (ref "R42") (pin "1") (pinfunction "1_1") (pintype "passive"))
      (node (ref "R5") (pin "1") (pinfunction "1_1") (pintype "passive"))
      (node (ref "U1") (pin "108") (pinfunction "VDD_108") (pintype "passive"))
      (node (ref "U1") (pin "121") (pinfunction "VDD_121") (pintype "passive"))
      (node (ref "U1") (pin "131") (pinfunction "VDD_131") (pintype "passive"))
      (node (ref "U1") (pin "144") (pinfunction "VDD_144") (pintype "passive"))
      (node (ref "U1") (pin "17") (pinfunction "VDD_17") (pintype "passive"))
      (node (ref "U1") (pin "39") (pinfunction "VDD_39") (pintype "passive"))
      (node (ref "U1") (pin "52") (pinfunction "VDD_52") (pintype "passive"))
      (node (ref "U1") (pin "62") (pinfunction "VDD_62") (pintype "passive"))
      (node (ref "U1") (pin "72") (pinfunction "VDD_72") (pintype "passive"))
      (node (ref "U1") (pin "84") (pinfunction "VDD_84") (pintype "passive"))
      (node (ref "U1") (pin "95") (pinfunction "VDD_95") (pintype "passive"))
      (node (ref "U2") (pin "1") (pinfunction "VCC_1") (pintype "passive"))
      (node (ref "U4") (pin "1") (pinfunction "VCC_1") (pintype "passive"))
      (node (ref "U6") (pin "16") (pinfunction "VCC_16") (pintype "passive"))
      (node (ref "U7") (pin "2") (pinfunction "OUT_2") (pintype "passive"))
      (node (ref "U8") (pin "8") (pinfunction "VCC_8") (pintype "power_in"))
      (node (ref "U9") (pin "1") (pinfunction "VDD_1") (pintype "passive"))
      (node (ref "U9") (pin "2") (pinfunction "VDD_2") (pintype "passive"))
    )
    (net (code "169") (name "VCCIN") (class "Default")
      (node (ref "P9") (pin "2") (pinfunction "2_2") (pintype "passive"))
      (node (ref "S1") (pin "3") (pinfunction "A3_3") (pintype "passive"))
      (node (ref "U5") (pin "1") (pinfunction "VCC_1") (pintype "passive"))
    )
    (net (code "170") (name "unconnected-(J1-MH1-Pad10)") (class "Default")
      (node (ref "J1") (pin "10") (pinfunction "MH1_10") (pintype "passive"))
    )
    (net (code "171") (name "unconnected-(J1-MH2-Pad11)") (class "Default")
      (node (ref "J1") (pin "11") (pinfunction "MH2_11") (pintype "passive"))
    )
    (net (code "172") (name "unconnected-(J1-Pad1)") (class "Default")
      (node (ref "J1") (pin "1") (pinfunction "1_1") (pintype "passive"))
    )
    (net (code "173") (name "unconnected-(J1-Pad9)") (class "Default")
      (node (ref "J1") (pin "9") (pinfunction "9_9") (pintype "passive"))
    )
    (net (code "174") (name "unconnected-(J2-MH1-Pad10)") (class "Default")
      (node (ref "J2") (pin "10") (pinfunction "MH1_10") (pintype "passive"))
    )
    (net (code "175") (name "unconnected-(J2-MH2-Pad11)") (class "Default")
      (node (ref "J2") (pin "11") (pinfunction "MH2_11") (pintype "passive"))
    )
    (net (code "176") (name "unconnected-(J2-Pad1)") (class "Default")
      (node (ref "J2") (pin "1") (pinfunction "1_1") (pintype "passive"))
    )
    (net (code "177") (name "unconnected-(J2-Pad9)") (class "Default")
      (node (ref "J2") (pin "9") (pinfunction "9_9") (pintype "passive"))
    )
    (net (code "178") (name "unconnected-(P2-Pad11)") (class "Default")
      (node (ref "P2") (pin "11") (pinfunction "11_11") (pintype "passive"))
    )
    (net (code "179") (name "unconnected-(P10-Pad3)") (class "Default")
      (node (ref "P10") (pin "3") (pinfunction "3_3") (pintype "passive"))
    )
    (net (code "180") (name "unconnected-(P11-Pad2)") (class "Default")
      (node (ref "P11") (pin "2") (pinfunction "2_2") (pintype "passive"))
    )
    (net (code "181") (name "unconnected-(P11-Pad4)") (class "Default")
      (node (ref "P11") (pin "4") (pinfunction "4_4") (pintype "passive"))
    )
    (net (code "182") (name "unconnected-(P11-Pad6)") (class "Default")
      (node (ref "P11") (pin "6") (pinfunction "6_6") (pintype "passive"))
    )
    (net (code "183") (name "unconnected-(P11-Pad8)") (class "Default")
      (node (ref "P11") (pin "8") (pinfunction "8_8") (pintype "passive"))
    )
    (net (code "184") (name "unconnected-(P13-Pad2)") (class "Default")
      (node (ref "P13") (pin "2") (pinfunction "2_2") (pintype "passive"))
    )
    (net (code "185") (name "unconnected-(P13-Pad4)") (class "Default")
      (node (ref "P13") (pin "4") (pinfunction "4_4") (pintype "passive"))
    )
    (net (code "186") (name "unconnected-(P14-Pad4)") (class "Default")
      (node (ref "P14") (pin "4") (pinfunction "4_4") (pintype "passive"))
    )
    (net (code "187") (name "unconnected-(P14-Pad6)") (class "Default")
      (node (ref "P14") (pin "6") (pinfunction "6_6") (pintype "passive"))
    )
    (net (code "188") (name "unconnected-(P14-Pad8)") (class "Default")
      (node (ref "P14") (pin "8") (pinfunction "8_8") (pintype "passive"))
    )
    (net (code "189") (name "unconnected-(P14-Pad10)") (class "Default")
      (node (ref "P14") (pin "10") (pinfunction "10_10") (pintype "passive"))
    )
    (net (code "190") (name "unconnected-(P16-Pad4)") (class "Default")
      (node (ref "P16") (pin "4") (pinfunction "4_4") (pintype "passive"))
    )
    (net (code "191") (name "unconnected-(P16-Pad6)") (class "Default")
      (node (ref "P16") (pin "6") (pinfunction "6_6") (pintype "passive"))
    )
    (net (code "192") (name "unconnected-(P16-Pad8)") (class "Default")
      (node (ref "P16") (pin "8") (pinfunction "8_8") (pintype "passive"))
    )
    (net (code "193") (name "unconnected-(P16-Pad10)") (class "Default")
      (node (ref "P16") (pin "10") (pinfunction "10_10") (pintype "passive"))
    )
    (net (code "194") (name "unconnected-(P17-Pad4)") (class "Default")
      (node (ref "P17") (pin "4") (pinfunction "4_4") (pintype "passive"))
    )
    (net (code "195") (name "unconnected-(P17-Pad6)") (class "Default")
      (node (ref "P17") (pin "6") (pinfunction "6_6") (pintype "passive"))
    )
    (net (code "196") (name "unconnected-(P17-Pad8)") (class "Default")
      (node (ref "P17") (pin "8") (pinfunction "8_8") (pintype "passive"))
    )
    (net (code "197") (name "unconnected-(P17-Pad10)") (class "Default")
      (node (ref "P17") (pin "10") (pinfunction "10_10") (pintype "passive"))
    )
    (net (code "198") (name "unconnected-(S1-A1-Pad1)") (class "Default")
      (node (ref "S1") (pin "1") (pinfunction "A1_1") (pintype "passive"))
    )
    (net (code "199") (name "unconnected-(S1-B3-Pad4)") (class "Default")
      (node (ref "S1") (pin "4") (pinfunction "B3_4") (pintype "passive"))
    )
    (net (code "200") (name "unconnected-(U1-NC-Pad106)") (class "Default")
      (node (ref "U1") (pin "106") (pinfunction "NC_106") (pintype "passive+no_connect"))
    )
    (net (code "201") (name "unconnected-(U3-CTS_N-Pad11)") (class "Default")
      (node (ref "U3") (pin "11") (pinfunction "CTS_N_11") (pintype "passive"))
    )
    (net (code "202") (name "unconnected-(U3-DCD_N-Pad10)") (class "Default")
      (node (ref "U3") (pin "10") (pinfunction "DCD_N_10") (pintype "passive"))
    )
    (net (code "203") (name "unconnected-(U3-DSR_N-Pad9)") (class "Default")
      (node (ref "U3") (pin "9") (pinfunction "DSR_N_9") (pintype "passive"))
    )
    (net (code "204") (name "unconnected-(U3-EE_CLK-Pad13)") (class "Default")
      (node (ref "U3") (pin "13") (pinfunction "EE_CLK_13") (pintype "passive"))
    )
    (net (code "205") (name "unconnected-(U3-EE_DATA-Pad14)") (class "Default")
      (node (ref "U3") (pin "14") (pinfunction "EE_DATA_14") (pintype "passive"))
    )
    (net (code "206") (name "unconnected-(U3-RI_N-Pad6)") (class "Default")
      (node (ref "U3") (pin "6") (pinfunction "RI_N_6") (pintype "passive"))
    )
    (net (code "207") (name "unconnected-(U3-SHTD_N-Pad12)") (class "Default")
      (node (ref "U3") (pin "12") (pinfunction "SHTD_N_12") (pintype "passive"))
    )
    (net (code "208") (name "unconnected-(U5-NC-Pad4)") (class "Default")
      (node (ref "U5") (pin "4") (pinfunction "NC_4") (pintype "passive"))
    )
    (net (code "209") (name "unconnected-(U9-NC-Pad11)") (class "Default")
      (node (ref "U9") (pin "11") (pinfunction "NC_11") (pintype "passive"))
    )
    (net (code "210") (name "unconnected-(U9-NC-Pad17)") (class "Default")
      (node (ref "U9") (pin "17") (pinfunction "NC_17") (pintype "passive"))
    )
    (net (code "211") (name "unconnected-(U9-NC-Pad19)") (class "Default")
      (node (ref "U9") (pin "19") (pinfunction "NC_19") (pintype "passive"))
    )
  )
)
